# S7G7_footprint_simplified_w_ethernet_v1p.net
KiCad netlist of a schematic drawn in EAGLE
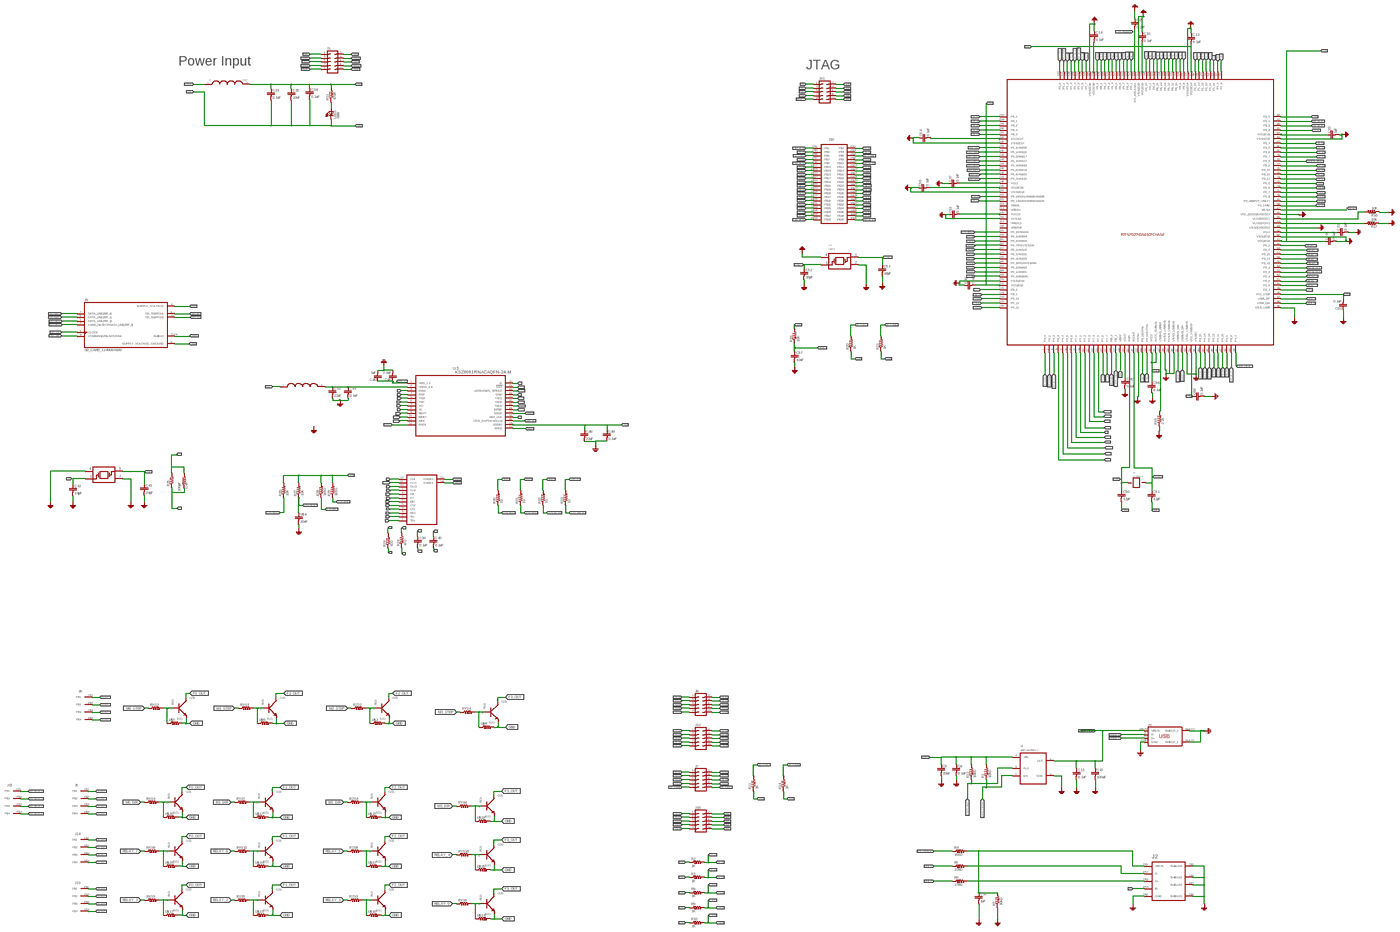
[diagram p0: schematic, sheet 1, overview]
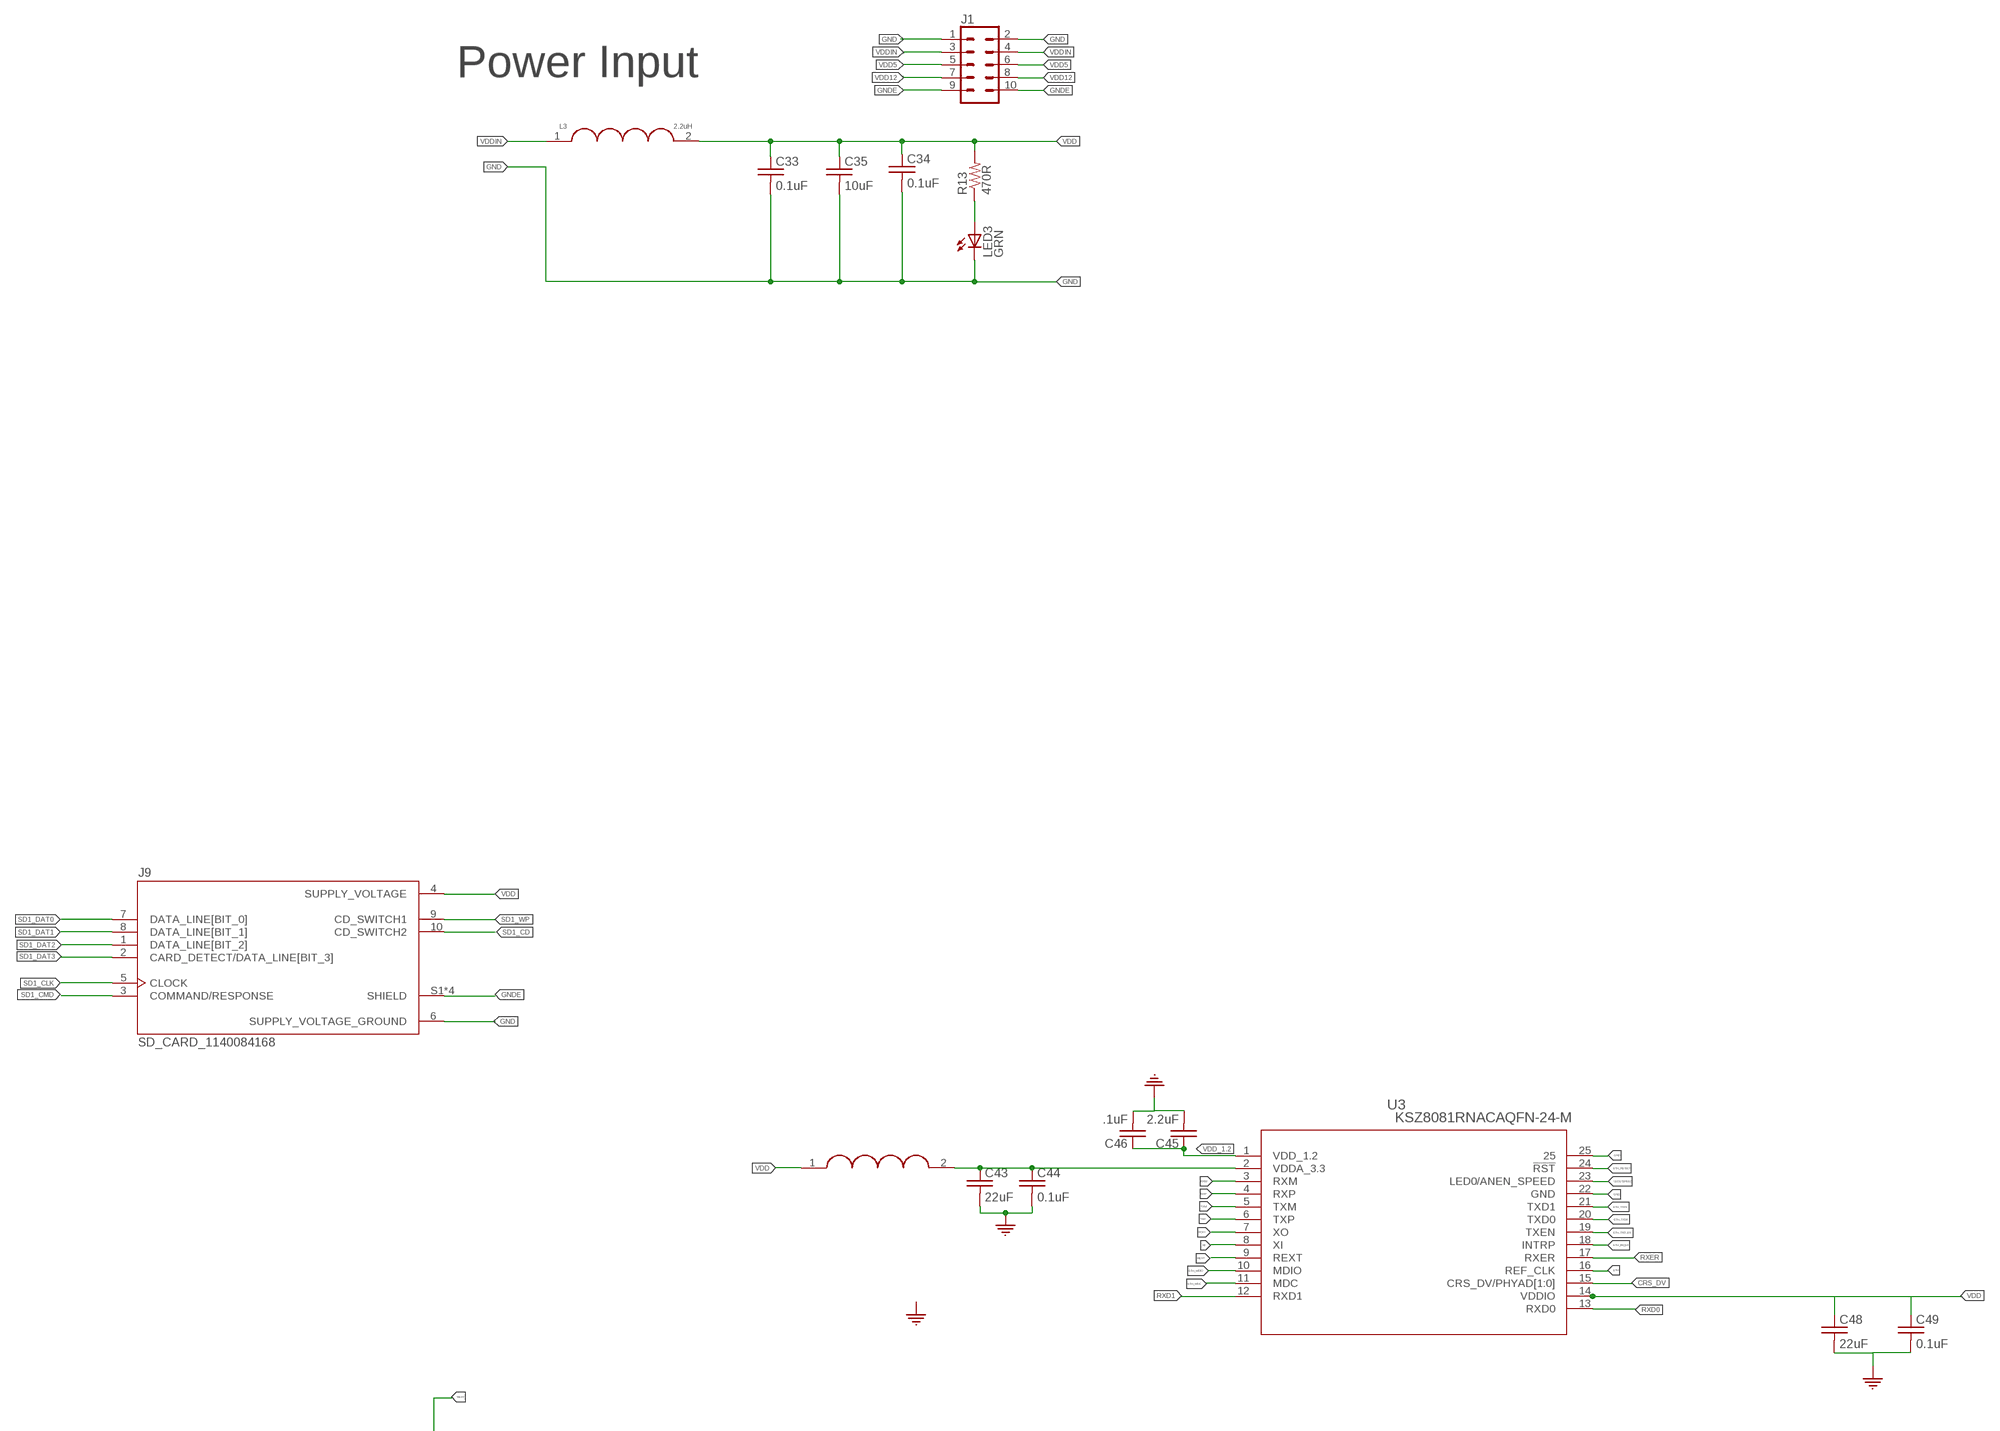
[diagram p1: schematic, sheet 1, part 1 of 4]
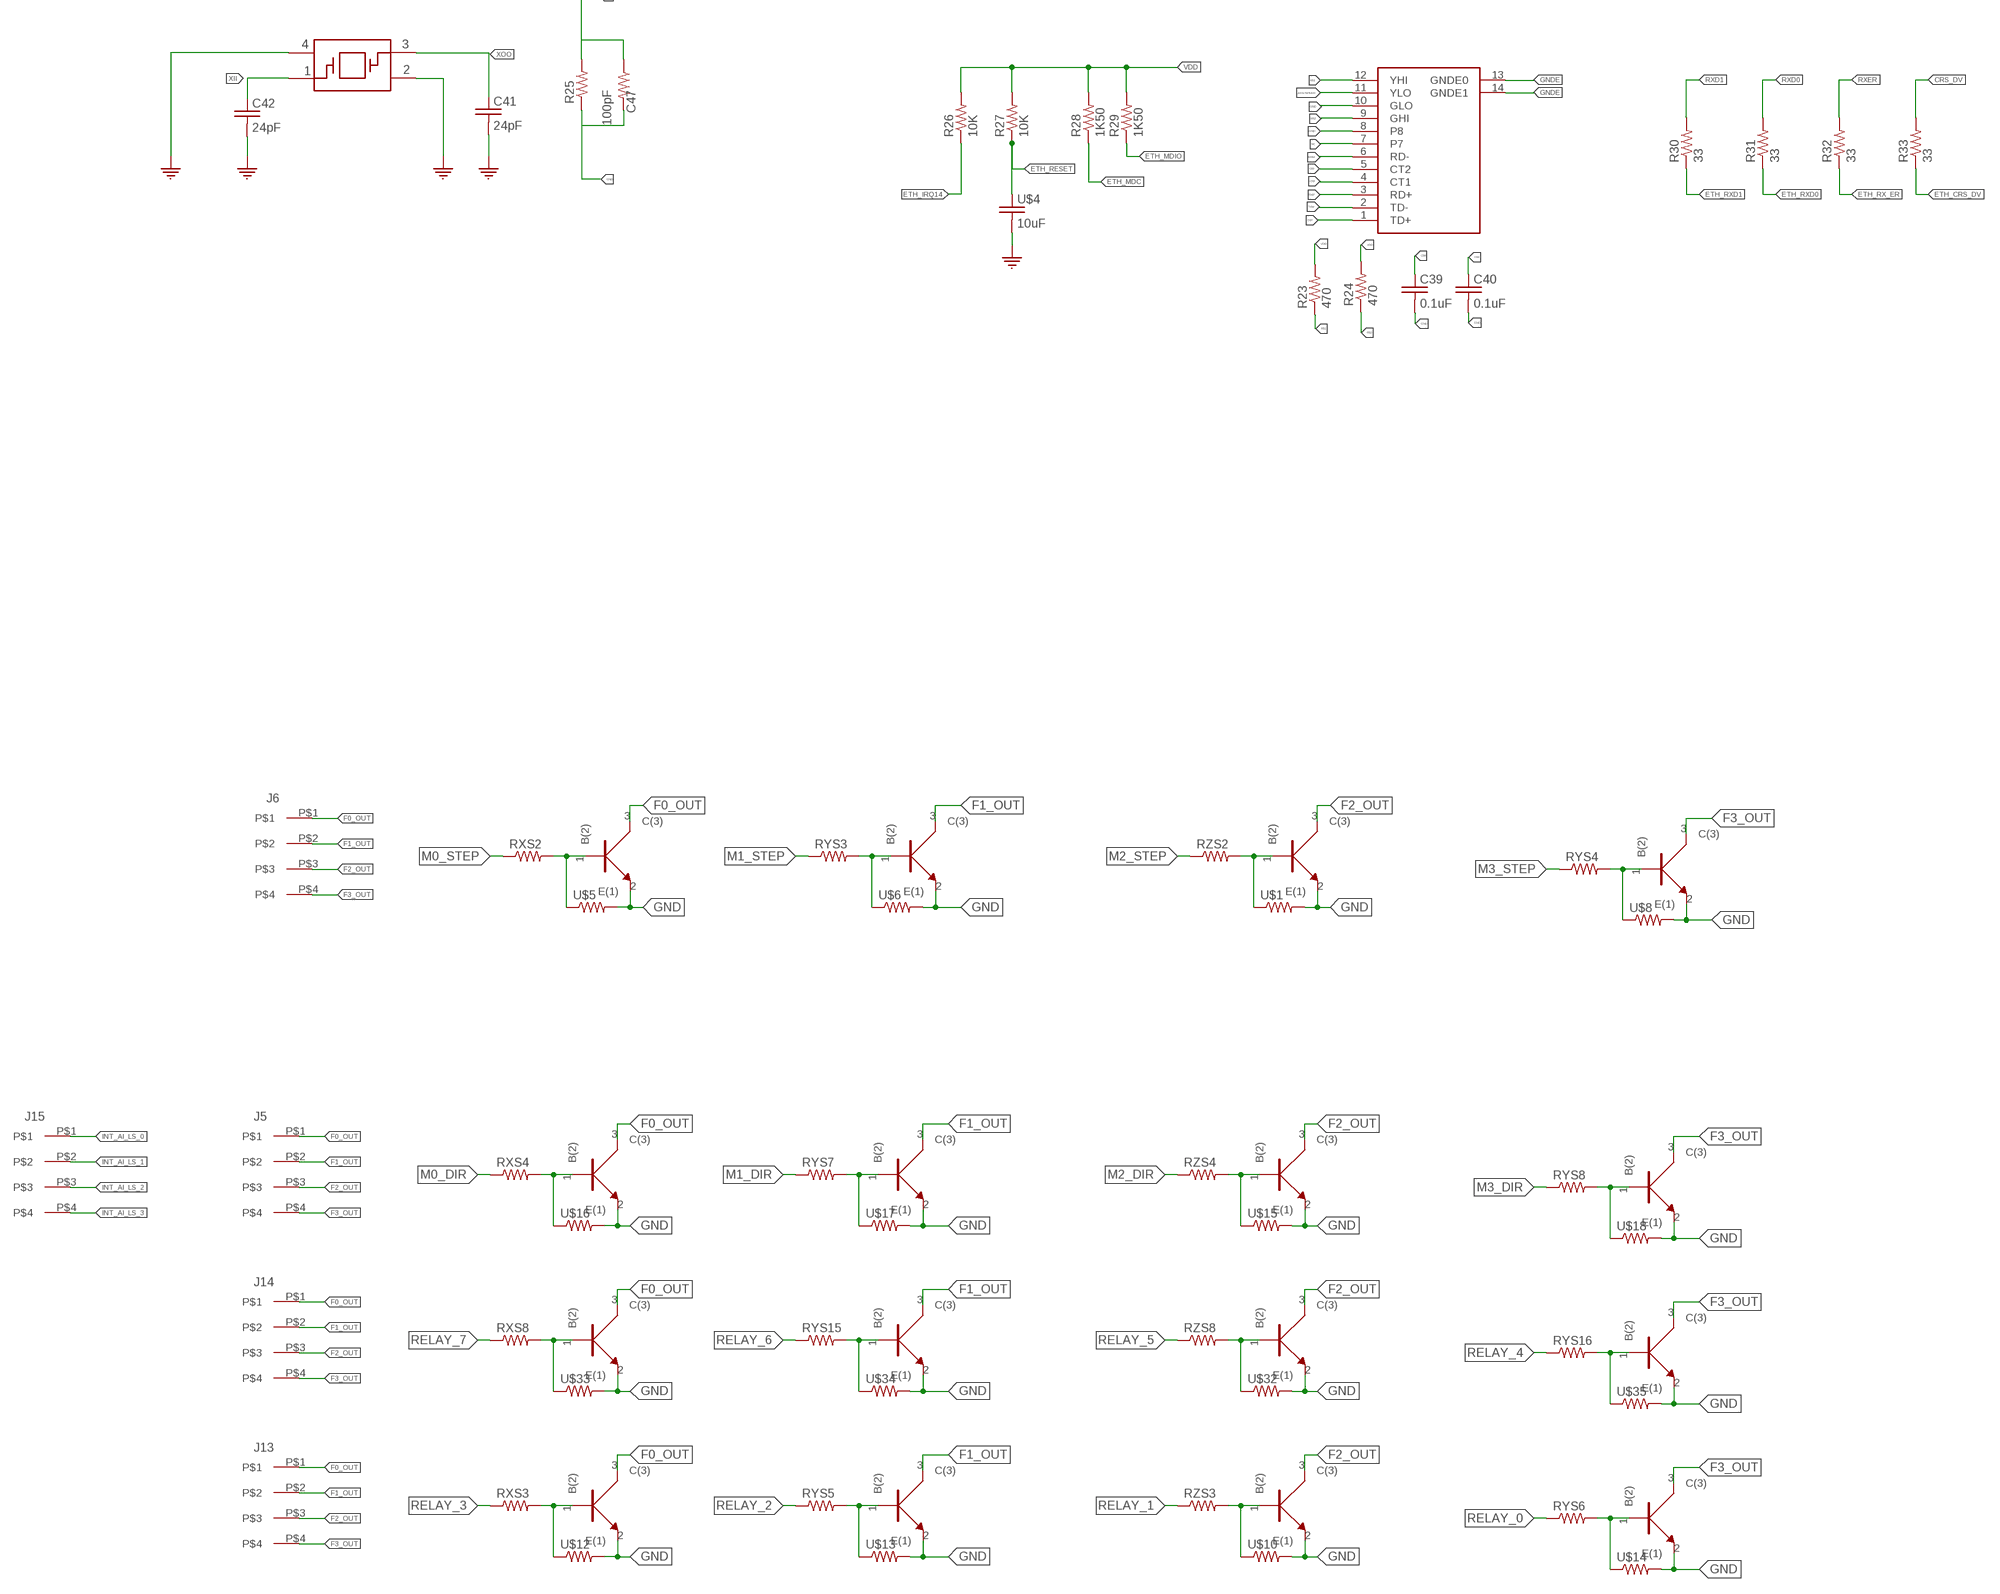
[diagram p2: schematic, sheet 1, part 2 of 4]
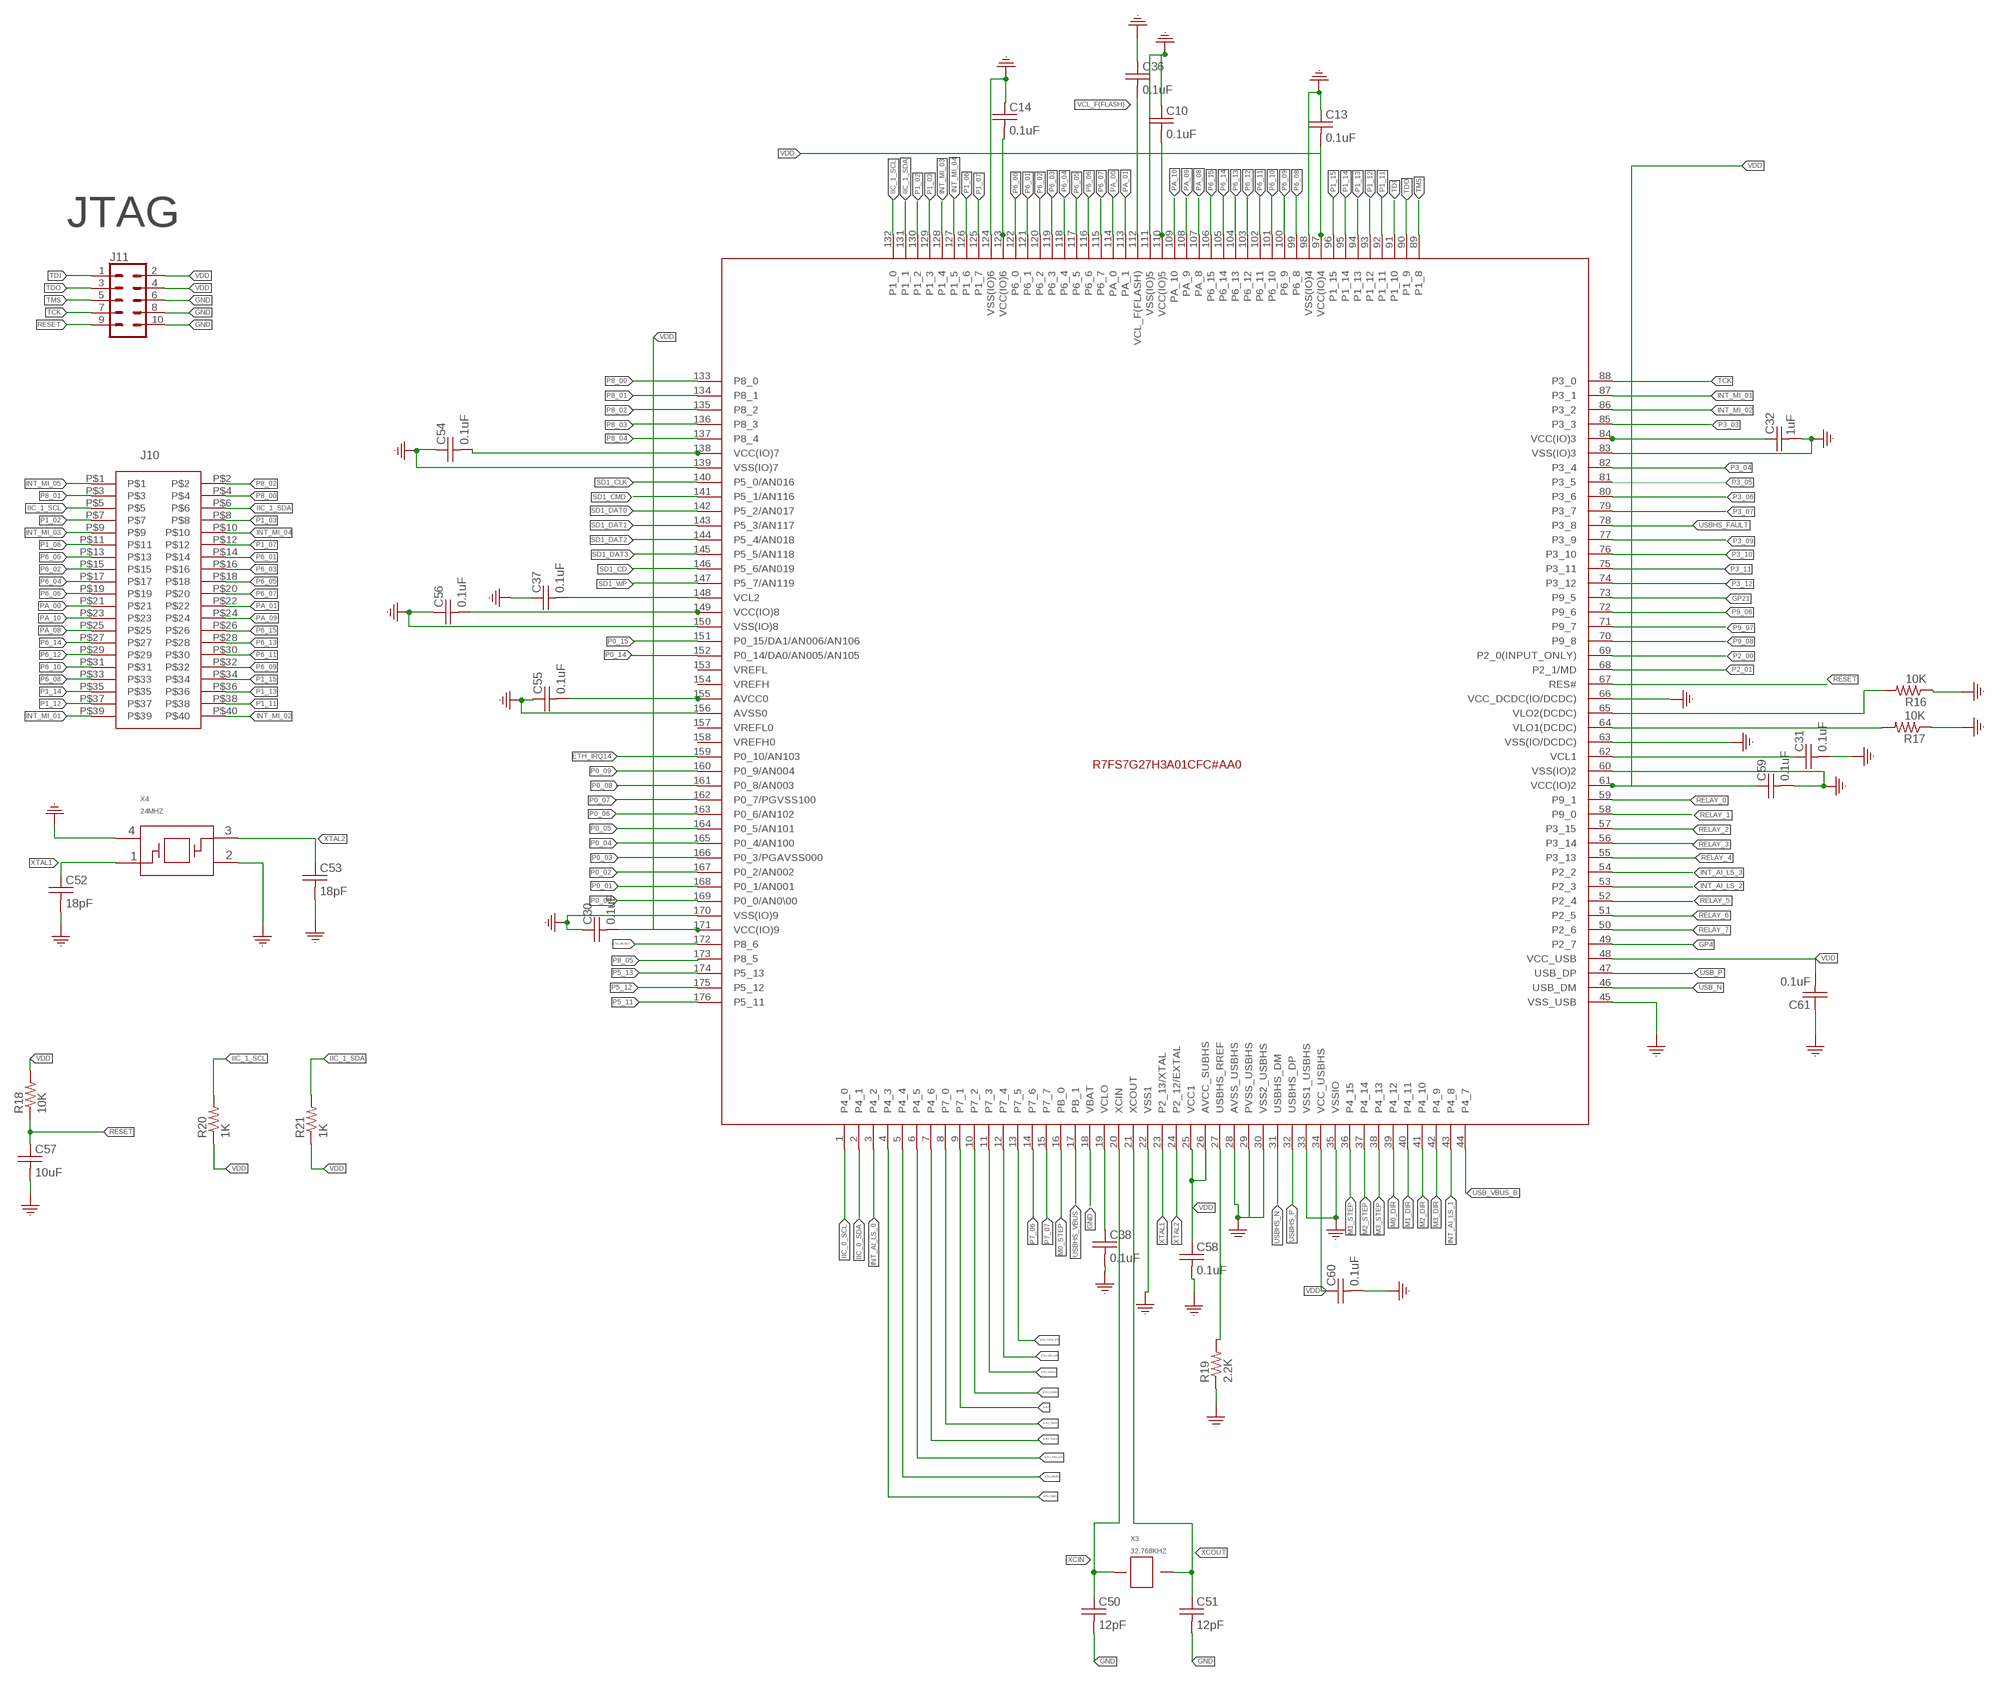
[diagram p3: schematic, sheet 1, part 3 of 4]
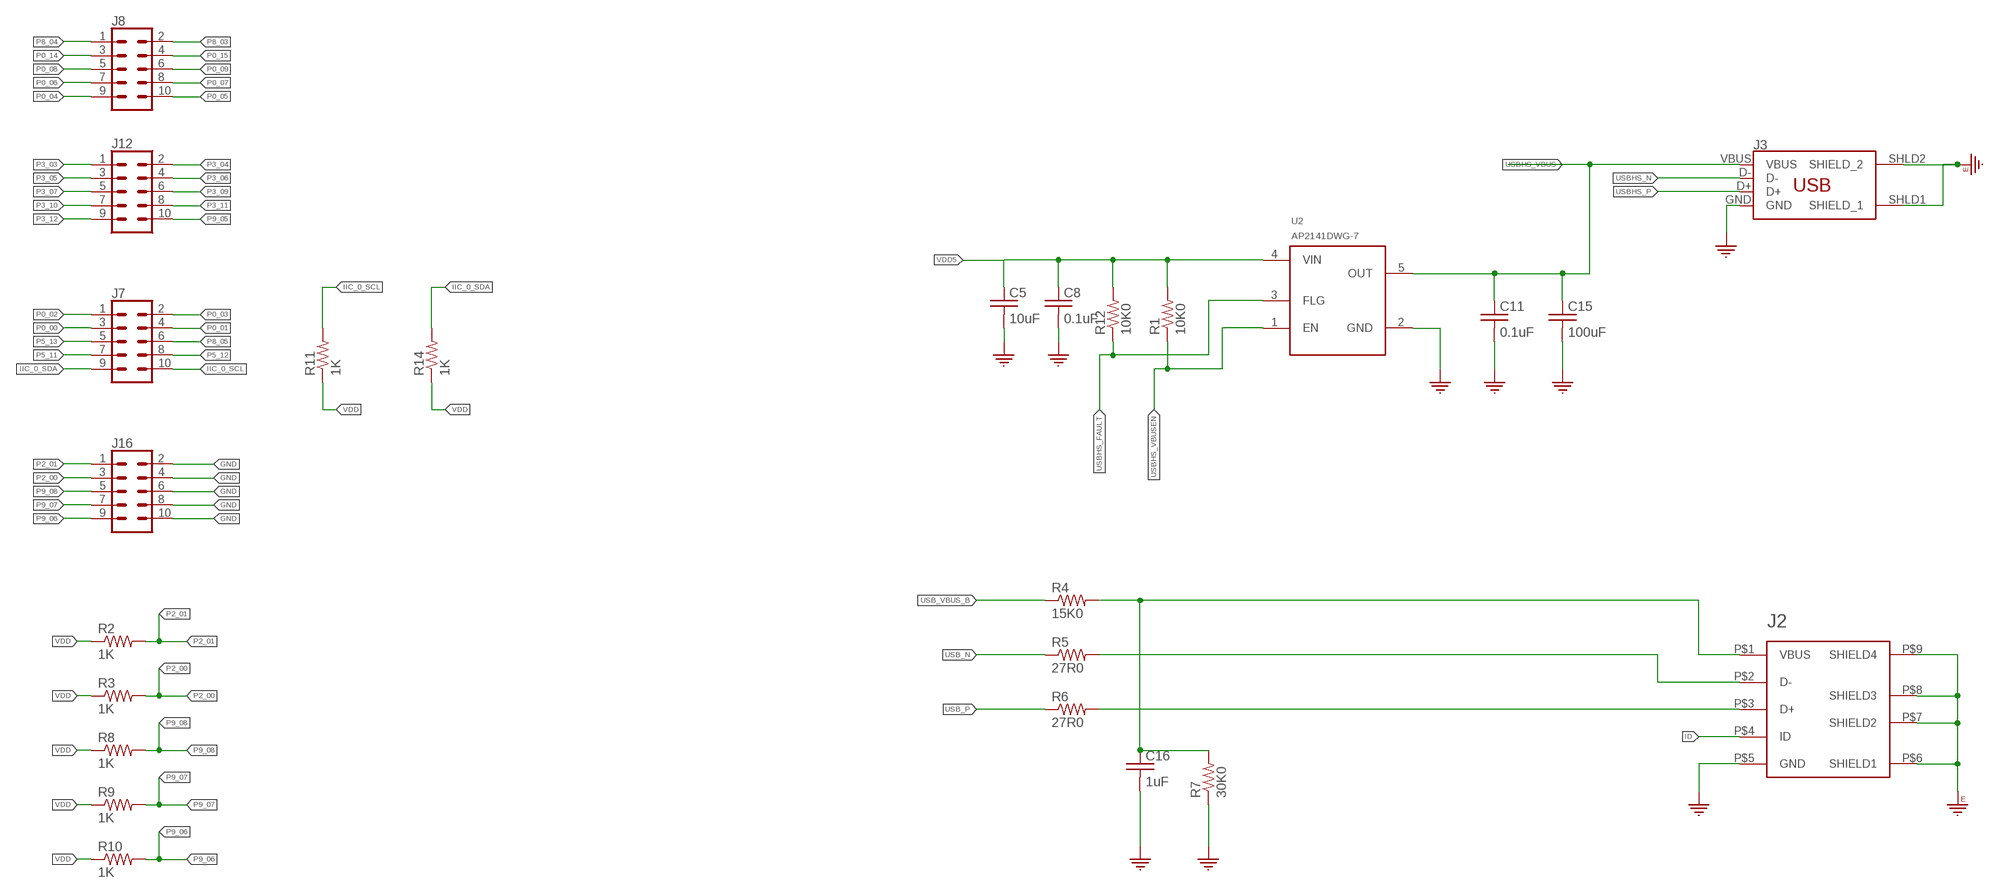
[diagram p4: schematic, sheet 1, part 4 of 4]

(export (version "E")
  (design (tool "Eeschema 10.0.6"))
  (components
    (comp (ref "C5")
      (value "10uF")
      (footprint "eagle-import:0402")
      (libsource (lib "eagle-import") (part "C_0402"))
    )
    (comp (ref "C8")
      (value "0.1uF")
      (footprint "eagle-import:0402")
      (libsource (lib "eagle-import") (part "C_0402"))
    )
    (comp (ref "C10")
      (value "0.1uF")
      (footprint "eagle-import:0402")
      (libsource (lib "eagle-import") (part "C_0402"))
    )
    (comp (ref "C11")
      (value "0.1uF")
      (footprint "eagle-import:0402")
      (libsource (lib "eagle-import") (part "C_0402"))
    )
    (comp (ref "C13")
      (value "0.1uF")
      (footprint "eagle-import:0402")
      (libsource (lib "eagle-import") (part "C_0402"))
    )
    (comp (ref "C14")
      (value "0.1uF")
      (footprint "eagle-import:0402")
      (libsource (lib "eagle-import") (part "C_0402"))
    )
    (comp (ref "C15")
      (value "100uF")
      (footprint "eagle-import:C1210")
      (libsource (lib "eagle-import") (part "C_1210"))
    )
    (comp (ref "C16")
      (value "1uF")
      (footprint "eagle-import:0402")
      (libsource (lib "eagle-import") (part "C_0402"))
    )
    (comp (ref "C30")
      (value "0.1uF")
      (footprint "eagle-import:0402")
      (libsource (lib "eagle-import") (part "C_0402"))
    )
    (comp (ref "C31")
      (value "0.1uF")
      (footprint "eagle-import:0402")
      (libsource (lib "eagle-import") (part "C_0402"))
    )
    (comp (ref "C32")
      (value "1uF")
      (footprint "eagle-import:0402")
      (libsource (lib "eagle-import") (part "C_0402"))
    )
    (comp (ref "C33")
      (value "0.1uF")
      (footprint "eagle-import:0402")
      (libsource (lib "eagle-import") (part "C_0402"))
    )
    (comp (ref "C34")
      (value "0.1uF")
      (footprint "eagle-import:0402")
      (libsource (lib "eagle-import") (part "C_0402"))
    )
    (comp (ref "C35")
      (value "10uF")
      (footprint "eagle-import:0402")
      (libsource (lib "eagle-import") (part "C_0402"))
    )
    (comp (ref "C36")
      (value "0.1uF")
      (footprint "eagle-import:0402")
      (libsource (lib "eagle-import") (part "C_0402"))
    )
    (comp (ref "C37")
      (value "0.1uF")
      (footprint "eagle-import:0402")
      (libsource (lib "eagle-import") (part "C_0402"))
    )
    (comp (ref "C38")
      (value "0.1uF")
      (footprint "eagle-import:0402")
      (libsource (lib "eagle-import") (part "C_0402"))
    )
    (comp (ref "C39")
      (value "0.1uF")
      (footprint "eagle-import:0402")
      (libsource (lib "eagle-import") (part "C_0402"))
    )
    (comp (ref "C40")
      (value "0.1uF")
      (footprint "eagle-import:0402")
      (libsource (lib "eagle-import") (part "C_0402"))
    )
    (comp (ref "C41")
      (value "24pF")
      (footprint "eagle-import:0402")
      (libsource (lib "eagle-import") (part "C_0402"))
    )
    (comp (ref "C42")
      (value "24pF")
      (footprint "eagle-import:0402")
      (libsource (lib "eagle-import") (part "C_0402"))
    )
    (comp (ref "C43")
      (value "22uF")
      (footprint "eagle-import:0603")
      (libsource (lib "eagle-import") (part "C_0603"))
    )
    (comp (ref "C44")
      (value "0.1uF")
      (footprint "eagle-import:0402")
      (libsource (lib "eagle-import") (part "C_0402"))
    )
    (comp (ref "C45")
      (value "2.2uF")
      (footprint "eagle-import:0402")
      (libsource (lib "eagle-import") (part "C_0402"))
    )
    (comp (ref "C46")
      (value ".1uF")
      (footprint "eagle-import:0402")
      (libsource (lib "eagle-import") (part "C_0402"))
    )
    (comp (ref "C47")
      (value "100pF")
      (footprint "eagle-import:0402")
      (libsource (lib "eagle-import") (part "R_0402"))
    )
    (comp (ref "C48")
      (value "22uF")
      (footprint "eagle-import:0603")
      (libsource (lib "eagle-import") (part "C_0603"))
    )
    (comp (ref "C49")
      (value "0.1uF")
      (footprint "eagle-import:0402")
      (libsource (lib "eagle-import") (part "C_0402"))
    )
    (comp (ref "C50")
      (value "12pF")
      (footprint "eagle-import:0402")
      (libsource (lib "eagle-import") (part "C_0402"))
    )
    (comp (ref "C51")
      (value "12pF")
      (footprint "eagle-import:0402")
      (libsource (lib "eagle-import") (part "C_0402"))
    )
    (comp (ref "C52")
      (value "18pF")
      (footprint "eagle-import:0402")
      (libsource (lib "eagle-import") (part "C_0402"))
    )
    (comp (ref "C53")
      (value "18pF")
      (footprint "eagle-import:0402")
      (libsource (lib "eagle-import") (part "C_0402"))
    )
    (comp (ref "C54")
      (value "0.1uF")
      (footprint "eagle-import:0402")
      (libsource (lib "eagle-import") (part "C_0402"))
    )
    (comp (ref "C55")
      (value "0.1uF")
      (footprint "eagle-import:0402")
      (libsource (lib "eagle-import") (part "C_0402"))
    )
    (comp (ref "C56")
      (value "0.1uF")
      (footprint "eagle-import:0402")
      (libsource (lib "eagle-import") (part "C_0402"))
    )
    (comp (ref "C57")
      (value "10uF")
      (footprint "eagle-import:0402")
      (libsource (lib "eagle-import") (part "C_0402"))
    )
    (comp (ref "C58")
      (value "0.1uF")
      (footprint "eagle-import:0402")
      (libsource (lib "eagle-import") (part "C_0402"))
    )
    (comp (ref "C59")
      (value "0.1uF")
      (footprint "eagle-import:0402")
      (libsource (lib "eagle-import") (part "C_0402"))
    )
    (comp (ref "C60")
      (value "0.1uF")
      (footprint "eagle-import:0402")
      (libsource (lib "eagle-import") (part "C_0402"))
    )
    (comp (ref "C61")
      (value "0.1uF")
      (footprint "eagle-import:0402")
      (libsource (lib "eagle-import") (part "C_0402"))
    )
    (comp (ref "FB2/2")
      (value "FB_0805_120_OHM")
      (footprint "eagle-import:0805")
      (libsource (lib "eagle-import") (part "FB_0805_120_OHM"))
    )
    (comp (ref "J1")
      (value "CONN_05X2PTH")
      (footprint "eagle-import:2X5")
      (libsource (lib "eagle-import") (part "CONN_05X2PTH"))
    )
    (comp (ref "J2")
      (value "USB_MICRO-B")
      (footprint "eagle-import:USB_MICRO-B")
      (libsource (lib "eagle-import") (part "USB_MICRO-B"))
    )
    (comp (ref "J3")
      (value "USB_A")
      (footprint "eagle-import:USB_A_SMT")
      (libsource (lib "eagle-import") (part "USB_A"))
    )
    (comp (ref "J4")
      (value "RJ45_WITH_ELEC")
      (footprint "eagle-import:RJ45_TH_ELEC")
      (libsource (lib "eagle-import") (part "RJ45_WITH_ELEC"))
    )
    (comp (ref "J5")
      (value "3.81MM_1_X_4_RT_ANGLE_PLUG_HEADER")
      (footprint "eagle-import:1X4_3.81MM_PITCH")
      (libsource (lib "eagle-import") (part "3.81MM_1_X_4_RT_ANGLE_PLUG_HEADER"))
    )
    (comp (ref "J6")
      (value "3.81MM_1_X_4_RT_ANGLE_PLUG_HEADER")
      (footprint "eagle-import:1X4_3.81MM_PITCH")
      (libsource (lib "eagle-import") (part "3.81MM_1_X_4_RT_ANGLE_PLUG_HEADER"))
    )
    (comp (ref "J7")
      (value "CONN_05X2NO_SILK")
      (footprint "eagle-import:2X5_NOSILK")
      (libsource (lib "eagle-import") (part "CONN_05X2NO_SILK"))
    )
    (comp (ref "J8")
      (value "CONN_05X2NO_SILK")
      (footprint "eagle-import:2X5_NOSILK")
      (libsource (lib "eagle-import") (part "CONN_05X2NO_SILK"))
    )
    (comp (ref "J9")
      (value "SD_CARD_1140084168")
      (footprint "eagle-import:AMPHENOL_1140084168")
      (fields
        (field (name "DIGI-KEY_PART_NUMBER") "114-00841-68-1-ND")
        (field (name "MF") "Amphenol ICC")
        (field (name "MP") "114-00841-68")
      )
      (libsource (lib "eagle-import") (part "SD_CARD_1140084168"))
    )
    (comp (ref "J10")
      (value "HEADER_2_X_20_GENERIC")
      (footprint "eagle-import:HEADER_2_X_20_.1_INCH")
      (libsource (lib "eagle-import") (part "HEADER_2_X_20_GENERIC"))
    )
    (comp (ref "J11")
      (value "CONN_05X2PTH")
      (footprint "eagle-import:2X5")
      (libsource (lib "eagle-import") (part "CONN_05X2PTH"))
    )
    (comp (ref "J12")
      (value "CONN_05X2NO_SILK")
      (footprint "eagle-import:2X5_NOSILK")
      (libsource (lib "eagle-import") (part "CONN_05X2NO_SILK"))
    )
    (comp (ref "J13")
      (value "3.81MM_1_X_4_RT_ANGLE_PLUG_HEADER")
      (footprint "eagle-import:1X4_3.81MM_PITCH")
      (libsource (lib "eagle-import") (part "3.81MM_1_X_4_RT_ANGLE_PLUG_HEADER"))
    )
    (comp (ref "J14")
      (value "3.81MM_1_X_4_RT_ANGLE_PLUG_HEADER")
      (footprint "eagle-import:1X4_3.81MM_PITCH")
      (libsource (lib "eagle-import") (part "3.81MM_1_X_4_RT_ANGLE_PLUG_HEADER"))
    )
    (comp (ref "J15")
      (value "3.81MM_1_X_4_RT_ANGLE_PLUG_HEADER")
      (footprint "eagle-import:1X4_3.81MM_PITCH")
      (libsource (lib "eagle-import") (part "3.81MM_1_X_4_RT_ANGLE_PLUG_HEADER"))
    )
    (comp (ref "J16")
      (value "CONN_05X2SHD_SMD")
      (footprint "eagle-import:2X5-SHROUDED_SMD")
      (libsource (lib "eagle-import") (part "CONN_05X2SHD_SMD"))
    )
    (comp (ref "L3")
      (value "2.2uH")
      (footprint "eagle-import:1008_(2520_METRIC)")
      (libsource (lib "eagle-import") (part "INDUCTOR_1008_2.2_MH_1.3A"))
    )
    (comp (ref "LED3")
      (value "LED_0805_GREEN")
      (footprint "eagle-import:LED_0805_GREEN")
      (libsource (lib "eagle-import") (part "LED_0805_GREEN"))
    )
    (comp (ref "R1")
      (value "10K0")
      (footprint "eagle-import:0402")
      (libsource (lib "eagle-import") (part "R_0402"))
    )
    (comp (ref "R2")
      (value "1K")
      (footprint "eagle-import:0402")
      (libsource (lib "eagle-import") (part "R_0402"))
    )
    (comp (ref "R3")
      (value "1K")
      (footprint "eagle-import:0402")
      (libsource (lib "eagle-import") (part "R_0402"))
    )
    (comp (ref "R4")
      (value "15K0")
      (footprint "eagle-import:0402")
      (libsource (lib "eagle-import") (part "R_0402"))
    )
    (comp (ref "R5")
      (value "27R0")
      (footprint "eagle-import:0402")
      (libsource (lib "eagle-import") (part "R_0402"))
    )
    (comp (ref "R6")
      (value "27R0")
      (footprint "eagle-import:0402")
      (libsource (lib "eagle-import") (part "R_0402"))
    )
    (comp (ref "R7")
      (value "30K0")
      (footprint "eagle-import:0402")
      (libsource (lib "eagle-import") (part "R_0402"))
    )
    (comp (ref "R8")
      (value "1K")
      (footprint "eagle-import:0402")
      (libsource (lib "eagle-import") (part "R_0402"))
    )
    (comp (ref "R9")
      (value "1K")
      (footprint "eagle-import:0402")
      (libsource (lib "eagle-import") (part "R_0402"))
    )
    (comp (ref "R10")
      (value "1K")
      (footprint "eagle-import:0402")
      (libsource (lib "eagle-import") (part "R_0402"))
    )
    (comp (ref "R11")
      (value "1K")
      (footprint "eagle-import:0402")
      (libsource (lib "eagle-import") (part "R_0402"))
    )
    (comp (ref "R12")
      (value "10K0")
      (footprint "eagle-import:0402")
      (libsource (lib "eagle-import") (part "R_0402"))
    )
    (comp (ref "R13")
      (value "470R")
      (footprint "eagle-import:0402")
      (libsource (lib "eagle-import") (part "R_0402"))
    )
    (comp (ref "R14")
      (value "1K")
      (footprint "eagle-import:0402")
      (libsource (lib "eagle-import") (part "R_0402"))
    )
    (comp (ref "R16")
      (value "10K")
      (footprint "eagle-import:0402")
      (libsource (lib "eagle-import") (part "R_0402"))
    )
    (comp (ref "R17")
      (value "10K")
      (footprint "eagle-import:0402")
      (libsource (lib "eagle-import") (part "R_0402"))
    )
    (comp (ref "R18")
      (value "10K")
      (footprint "eagle-import:0402")
      (libsource (lib "eagle-import") (part "R_0402"))
    )
    (comp (ref "R19")
      (value "2.2K")
      (footprint "eagle-import:0402")
      (libsource (lib "eagle-import") (part "R_0402"))
    )
    (comp (ref "R20")
      (value "1K")
      (footprint "eagle-import:0402")
      (libsource (lib "eagle-import") (part "R_0402"))
    )
    (comp (ref "R21")
      (value "1K")
      (footprint "eagle-import:0402")
      (libsource (lib "eagle-import") (part "R_0402"))
    )
    (comp (ref "R23")
      (value "470")
      (footprint "eagle-import:0402")
      (libsource (lib "eagle-import") (part "R_0402"))
    )
    (comp (ref "R24")
      (value "470")
      (footprint "eagle-import:0402")
      (libsource (lib "eagle-import") (part "R_0402"))
    )
    (comp (ref "R25")
      (value "6k49")
      (footprint "eagle-import:0402")
      (libsource (lib "eagle-import") (part "R_0402"))
    )
    (comp (ref "R26")
      (value "10K")
      (footprint "eagle-import:0402")
      (libsource (lib "eagle-import") (part "R_0402"))
    )
    (comp (ref "R27")
      (value "10K")
      (footprint "eagle-import:0402")
      (libsource (lib "eagle-import") (part "R_0402"))
    )
    (comp (ref "R28")
      (value "1K50")
      (footprint "eagle-import:0402")
      (libsource (lib "eagle-import") (part "R_0402"))
    )
    (comp (ref "R29")
      (value "1K50")
      (footprint "eagle-import:0402")
      (libsource (lib "eagle-import") (part "R_0402"))
    )
    (comp (ref "R30")
      (value "33")
      (footprint "eagle-import:0402")
      (libsource (lib "eagle-import") (part "R_0402"))
    )
    (comp (ref "R31")
      (value "33")
      (footprint "eagle-import:0402")
      (libsource (lib "eagle-import") (part "R_0402"))
    )
    (comp (ref "R32")
      (value "33")
      (footprint "eagle-import:0402")
      (libsource (lib "eagle-import") (part "R_0402"))
    )
    (comp (ref "R33")
      (value "33")
      (footprint "eagle-import:0402")
      (libsource (lib "eagle-import") (part "R_0402"))
    )
    (comp (ref "RXS2")
      (value "1K")
      (footprint "eagle-import:0402")
      (libsource (lib "eagle-import") (part "R_0402"))
    )
    (comp (ref "RXS3")
      (value "1K")
      (footprint "eagle-import:0402")
      (libsource (lib "eagle-import") (part "R_0402"))
    )
    (comp (ref "RXS4")
      (value "1K")
      (footprint "eagle-import:0402")
      (libsource (lib "eagle-import") (part "R_0402"))
    )
    (comp (ref "RXS8")
      (value "1K")
      (footprint "eagle-import:0402")
      (libsource (lib "eagle-import") (part "R_0402"))
    )
    (comp (ref "RYS3")
      (value "1K")
      (footprint "eagle-import:0402")
      (libsource (lib "eagle-import") (part "R_0402"))
    )
    (comp (ref "RYS4")
      (value "1K")
      (footprint "eagle-import:0402")
      (libsource (lib "eagle-import") (part "R_0402"))
    )
    (comp (ref "RYS5")
      (value "1K")
      (footprint "eagle-import:0402")
      (libsource (lib "eagle-import") (part "R_0402"))
    )
    (comp (ref "RYS6")
      (value "1K")
      (footprint "eagle-import:0402")
      (libsource (lib "eagle-import") (part "R_0402"))
    )
    (comp (ref "RYS7")
      (value "1K")
      (footprint "eagle-import:0402")
      (libsource (lib "eagle-import") (part "R_0402"))
    )
    (comp (ref "RYS8")
      (value "1K")
      (footprint "eagle-import:0402")
      (libsource (lib "eagle-import") (part "R_0402"))
    )
    (comp (ref "RYS15")
      (value "1K")
      (footprint "eagle-import:0402")
      (libsource (lib "eagle-import") (part "R_0402"))
    )
    (comp (ref "RYS16")
      (value "1K")
      (footprint "eagle-import:0402")
      (libsource (lib "eagle-import") (part "R_0402"))
    )
    (comp (ref "RZS2")
      (value "1K")
      (footprint "eagle-import:0402")
      (libsource (lib "eagle-import") (part "R_0402"))
    )
    (comp (ref "RZS3")
      (value "1K")
      (footprint "eagle-import:0402")
      (libsource (lib "eagle-import") (part "R_0402"))
    )
    (comp (ref "RZS4")
      (value "1K")
      (footprint "eagle-import:0402")
      (libsource (lib "eagle-import") (part "R_0402"))
    )
    (comp (ref "RZS8")
      (value "1K")
      (footprint "eagle-import:0402")
      (libsource (lib "eagle-import") (part "R_0402"))
    )
    (comp (ref "U$1")
      (value "1K")
      (footprint "eagle-import:0402")
      (libsource (lib "eagle-import") (part "R_0402"))
    )
    (comp (ref "U$3")
      (value "XTAL_25_MHZ")
      (footprint "eagle-import:SMD_3225")
      (libsource (lib "eagle-import") (part "XTAL_25_MHZ"))
    )
    (comp (ref "U$4")
      (value "10uF")
      (footprint "eagle-import:0402")
      (libsource (lib "eagle-import") (part "C_0402"))
    )
    (comp (ref "U$5")
      (value "1K")
      (footprint "eagle-import:0402")
      (libsource (lib "eagle-import") (part "R_0402"))
    )
    (comp (ref "U$6")
      (value "1K")
      (footprint "eagle-import:0402")
      (libsource (lib "eagle-import") (part "R_0402"))
    )
    (comp (ref "U$8")
      (value "1K")
      (footprint "eagle-import:0402")
      (libsource (lib "eagle-import") (part "R_0402"))
    )
    (comp (ref "U$10")
      (value "1K")
      (footprint "eagle-import:0402")
      (libsource (lib "eagle-import") (part "R_0402"))
    )
    (comp (ref "U$12")
      (value "1K")
      (footprint "eagle-import:0402")
      (libsource (lib "eagle-import") (part "R_0402"))
    )
    (comp (ref "U$13")
      (value "1K")
      (footprint "eagle-import:0402")
      (libsource (lib "eagle-import") (part "R_0402"))
    )
    (comp (ref "U$14")
      (value "1K")
      (footprint "eagle-import:0402")
      (libsource (lib "eagle-import") (part "R_0402"))
    )
    (comp (ref "U$15")
      (value "1K")
      (footprint "eagle-import:0402")
      (libsource (lib "eagle-import") (part "R_0402"))
    )
    (comp (ref "U$16")
      (value "1K")
      (footprint "eagle-import:0402")
      (libsource (lib "eagle-import") (part "R_0402"))
    )
    (comp (ref "U$17")
      (value "1K")
      (footprint "eagle-import:0402")
      (libsource (lib "eagle-import") (part "R_0402"))
    )
    (comp (ref "U$18")
      (value "1K")
      (footprint "eagle-import:0402")
      (libsource (lib "eagle-import") (part "R_0402"))
    )
    (comp (ref "U$32")
      (value "1K")
      (footprint "eagle-import:0402")
      (libsource (lib "eagle-import") (part "R_0402"))
    )
    (comp (ref "U$33")
      (value "1K")
      (footprint "eagle-import:0402")
      (libsource (lib "eagle-import") (part "R_0402"))
    )
    (comp (ref "U$34")
      (value "1K")
      (footprint "eagle-import:0402")
      (libsource (lib "eagle-import") (part "R_0402"))
    )
    (comp (ref "U$35")
      (value "1K")
      (footprint "eagle-import:0402")
      (libsource (lib "eagle-import") (part "R_0402"))
    )
    (comp (ref "U2")
      (value "AP2141DWG-5")
      (footprint "eagle-import:SOT-23-5")
      (libsource (lib "eagle-import") (part "AP2141DWG-5"))
    )
    (comp (ref "U3")
      (value "KSZ8081RNACAQFN-24-M")
      (footprint "eagle-import:QFN-24-M")
      (fields (field (name "MANUFACTURER_PART_NUMBER") "KSZ8081RNACA"))
      (libsource (lib "eagle-import") (part "KSZ8081RNACAQFN-24-M"))
    )
    (comp (ref "U4")
      (value "S7G2_X_176")
      (footprint "eagle-import:LQFP176_24X24")
      (libsource (lib "eagle-import") (part "S7G2_X_176"))
    )
    (comp (ref "U7")
      (value "BC846BW")
      (footprint "eagle-import:SOT323")
      (libsource (lib "eagle-import") (part "BC846BW"))
    )
    (comp (ref "U8")
      (value "BC846BW")
      (footprint "eagle-import:SOT323")
      (libsource (lib "eagle-import") (part "BC846BW"))
    )
    (comp (ref "U9")
      (value "BC846BW")
      (footprint "eagle-import:SOT323")
      (libsource (lib "eagle-import") (part "BC846BW"))
    )
    (comp (ref "U10")
      (value "BC846BW")
      (footprint "eagle-import:SOT323")
      (libsource (lib "eagle-import") (part "BC846BW"))
    )
    (comp (ref "U12")
      (value "BC846BW")
      (footprint "eagle-import:SOT323")
      (libsource (lib "eagle-import") (part "BC846BW"))
    )
    (comp (ref "U13")
      (value "BC846BW")
      (footprint "eagle-import:SOT323")
      (libsource (lib "eagle-import") (part "BC846BW"))
    )
    (comp (ref "U14")
      (value "BC846BW")
      (footprint "eagle-import:SOT323")
      (libsource (lib "eagle-import") (part "BC846BW"))
    )
    (comp (ref "U15")
      (value "BC846BW")
      (footprint "eagle-import:SOT323")
      (libsource (lib "eagle-import") (part "BC846BW"))
    )
    (comp (ref "U16")
      (value "BC846BW")
      (footprint "eagle-import:SOT323")
      (libsource (lib "eagle-import") (part "BC846BW"))
    )
    (comp (ref "U17")
      (value "BC846BW")
      (footprint "eagle-import:SOT323")
      (libsource (lib "eagle-import") (part "BC846BW"))
    )
    (comp (ref "U18")
      (value "BC846BW")
      (footprint "eagle-import:SOT323")
      (libsource (lib "eagle-import") (part "BC846BW"))
    )
    (comp (ref "U19")
      (value "BC846BW")
      (footprint "eagle-import:SOT323")
      (libsource (lib "eagle-import") (part "BC846BW"))
    )
    (comp (ref "U32")
      (value "BC846BW")
      (footprint "eagle-import:SOT323")
      (libsource (lib "eagle-import") (part "BC846BW"))
    )
    (comp (ref "U33")
      (value "BC846BW")
      (footprint "eagle-import:SOT323")
      (libsource (lib "eagle-import") (part "BC846BW"))
    )
    (comp (ref "U34")
      (value "BC846BW")
      (footprint "eagle-import:SOT323")
      (libsource (lib "eagle-import") (part "BC846BW"))
    )
    (comp (ref "U35")
      (value "BC846BW")
      (footprint "eagle-import:SOT323")
      (libsource (lib "eagle-import") (part "BC846BW"))
    )
    (comp (ref "X3")
      (value "32.768KHZ")
      (footprint "eagle-import:SMD_X_2_PADS")
      (libsource (lib "eagle-import") (part "XTAL_32.768KHZ"))
    )
    (comp (ref "X4")
      (value "24MHZ")
      (footprint "eagle-import:SMD_3225")
      (libsource (lib "eagle-import") (part "XTAL_24_MHZ"))
    )
  )
  (nets
    (net (code "1") (name "C58") (class "Default")
      (node (ref "C39") (pin "P$1") (pinfunction "1_P$1") (pintype "passive"))
      (node (ref "J4") (pin "4") (pinfunction "CT1_4") (pintype "bidirectional"))
    )
    (net (code "2") (name "C60") (class "Default")
      (node (ref "C40") (pin "P$1") (pinfunction "1_P$1") (pintype "passive"))
      (node (ref "J4") (pin "5") (pinfunction "CT2_5") (pintype "bidirectional"))
    )
    (net (code "3") (name "CRS_DV") (class "Default")
      (node (ref "R33") (pin "P$2") (pinfunction "2_P$2") (pintype "passive"))
      (node (ref "U3") (pin "15") (pinfunction "CRS_DV/PHYAD[1:0]_15") (pintype "bidirectional"))
    )
    (net (code "4") (name "ETH") (class "Default")
      (node (ref "U3") (pin "16") (pinfunction "REF_CLK_16") (pintype "bidirectional"))
      (node (ref "U4") (pin "9") (pinfunction "P7_1_9") (pintype "bidirectional"))
    )
    (net (code "5") (name "ETH_CRS_DV") (class "Default")
      (node (ref "R33") (pin "P$1") (pinfunction "1_P$1") (pintype "passive"))
      (node (ref "U4") (pin "13") (pinfunction "P7_5_13") (pintype "bidirectional"))
    )
    (net (code "6") (name "ETH_IRQ14") (class "Default")
      (node (ref "R26") (pin "P$1") (pinfunction "1_P$1") (pintype "passive"))
      (node (ref "U3") (pin "18") (pinfunction "INTRP_18") (pintype "bidirectional"))
      (node (ref "U4") (pin "159") (pinfunction "P0_10/AN103_159") (pintype "bidirectional"))
    )
    (net (code "7") (name "ETH_MDC") (class "Default")
      (node (ref "R28") (pin "P$1") (pinfunction "1_P$1") (pintype "passive"))
      (node (ref "U3") (pin "11") (pinfunction "MDC_11") (pintype "input"))
      (node (ref "U4") (pin "4") (pinfunction "P4_3_4") (pintype "bidirectional"))
    )
    (net (code "8") (name "ETH_MDIO") (class "Default")
      (node (ref "R29") (pin "P$1") (pinfunction "1_P$1") (pintype "passive"))
      (node (ref "U3") (pin "10") (pinfunction "MDIO_10") (pintype "bidirectional"))
      (node (ref "U4") (pin "5") (pinfunction "P4_4_5") (pintype "bidirectional"))
    )
    (net (code "9") (name "ETH_RESET") (class "Default")
      (node (ref "R27") (pin "P$1") (pinfunction "1_P$1") (pintype "passive"))
      (node (ref "U$4") (pin "P$1") (pinfunction "1_P$1") (pintype "passive"))
      (node (ref "U3") (pin "24") (pinfunction "~{RST}_24") (pintype "input"))
      (node (ref "U4") (pin "172") (pinfunction "P8_6_172") (pintype "bidirectional"))
    )
    (net (code "10") (name "ETH_RXD0") (class "Default")
      (node (ref "R31") (pin "P$1") (pinfunction "1_P$1") (pintype "passive"))
      (node (ref "U4") (pin "10") (pinfunction "P7_2_10") (pintype "bidirectional"))
    )
    (net (code "11") (name "ETH_RXD1") (class "Default")
      (node (ref "R30") (pin "P$1") (pinfunction "1_P$1") (pintype "passive"))
      (node (ref "U4") (pin "11") (pinfunction "P7_3_11") (pintype "bidirectional"))
    )
    (net (code "12") (name "ETH_RX_ER") (class "Default")
      (node (ref "R32") (pin "P$1") (pinfunction "1_P$1") (pintype "passive"))
      (node (ref "U4") (pin "12") (pinfunction "P7_4_12") (pintype "bidirectional"))
    )
    (net (code "13") (name "ETH_TXD0") (class "Default")
      (node (ref "U3") (pin "20") (pinfunction "TXD0_20") (pintype "input"))
      (node (ref "U4") (pin "8") (pinfunction "P7_0_8") (pintype "bidirectional"))
    )
    (net (code "14") (name "ETH_TXD1") (class "Default")
      (node (ref "U3") (pin "21") (pinfunction "TXD1_21") (pintype "bidirectional"))
      (node (ref "U4") (pin "7") (pinfunction "P4_6_7") (pintype "bidirectional"))
    )
    (net (code "15") (name "ETH_TXD_EN") (class "Default")
      (node (ref "U3") (pin "19") (pinfunction "TXEN_19") (pintype "input"))
      (node (ref "U4") (pin "6") (pinfunction "P4_5_6") (pintype "bidirectional"))
    )
    (net (code "16") (name "F0_OUT") (class "Default")
      (node (ref "J13") (pin "P$1") (pinfunction "P$1_P$1") (pintype "bidirectional"))
      (node (ref "J14") (pin "P$1") (pinfunction "P$1_P$1") (pintype "bidirectional"))
      (node (ref "J5") (pin "P$1") (pinfunction "P$1_P$1") (pintype "bidirectional"))
      (node (ref "J6") (pin "P$1") (pinfunction "P$1_P$1") (pintype "bidirectional"))
      (node (ref "U13") (pin "3") (pinfunction "C(3)_3") (pintype "input"))
      (node (ref "U17") (pin "3") (pinfunction "C(3)_3") (pintype "input"))
      (node (ref "U33") (pin "3") (pinfunction "C(3)_3") (pintype "input"))
      (node (ref "U8") (pin "3") (pinfunction "C(3)_3") (pintype "input"))
    )
    (net (code "17") (name "F1_OUT") (class "Default")
      (node (ref "J13") (pin "P$2") (pinfunction "P$2_P$2") (pintype "bidirectional"))
      (node (ref "J14") (pin "P$2") (pinfunction "P$2_P$2") (pintype "bidirectional"))
      (node (ref "J5") (pin "P$2") (pinfunction "P$2_P$2") (pintype "bidirectional"))
      (node (ref "J6") (pin "P$2") (pinfunction "P$2_P$2") (pintype "bidirectional"))
      (node (ref "U14") (pin "3") (pinfunction "C(3)_3") (pintype "input"))
      (node (ref "U18") (pin "3") (pinfunction "C(3)_3") (pintype "input"))
      (node (ref "U34") (pin "3") (pinfunction "C(3)_3") (pintype "input"))
      (node (ref "U9") (pin "3") (pinfunction "C(3)_3") (pintype "input"))
    )
    (net (code "18") (name "F2_OUT") (class "Default")
      (node (ref "J13") (pin "P$3") (pinfunction "P$3_P$3") (pintype "bidirectional"))
      (node (ref "J14") (pin "P$3") (pinfunction "P$3_P$3") (pintype "bidirectional"))
      (node (ref "J5") (pin "P$3") (pinfunction "P$3_P$3") (pintype "bidirectional"))
      (node (ref "J6") (pin "P$3") (pinfunction "P$3_P$3") (pintype "bidirectional"))
      (node (ref "U12") (pin "3") (pinfunction "C(3)_3") (pintype "input"))
      (node (ref "U16") (pin "3") (pinfunction "C(3)_3") (pintype "input"))
      (node (ref "U32") (pin "3") (pinfunction "C(3)_3") (pintype "input"))
      (node (ref "U7") (pin "3") (pinfunction "C(3)_3") (pintype "input"))
    )
    (net (code "19") (name "F3_OUT") (class "Default")
      (node (ref "J13") (pin "P$4") (pinfunction "P$4_P$4") (pintype "bidirectional"))
      (node (ref "J14") (pin "P$4") (pinfunction "P$4_P$4") (pintype "bidirectional"))
      (node (ref "J5") (pin "P$4") (pinfunction "P$4_P$4") (pintype "bidirectional"))
      (node (ref "J6") (pin "P$4") (pinfunction "P$4_P$4") (pintype "bidirectional"))
      (node (ref "U10") (pin "3") (pinfunction "C(3)_3") (pintype "input"))
      (node (ref "U15") (pin "3") (pinfunction "C(3)_3") (pintype "input"))
      (node (ref "U19") (pin "3") (pinfunction "C(3)_3") (pintype "input"))
      (node (ref "U35") (pin "3") (pinfunction "C(3)_3") (pintype "input"))
    )
    (net (code "20") (name "GND") (class "Default")
      (node (ref "C10") (pin "P$1") (pinfunction "1_P$1") (pintype "passive"))
      (node (ref "C11") (pin "P$2") (pinfunction "2_P$2") (pintype "passive"))
      (node (ref "C13") (pin "P$1") (pinfunction "1_P$1") (pintype "passive"))
      (node (ref "C14") (pin "P$1") (pinfunction "1_P$1") (pintype "passive"))
      (node (ref "C15") (pin "2") (pinfunction "2_2") (pintype "passive"))
      (node (ref "C16") (pin "P$2") (pinfunction "2_P$2") (pintype "passive"))
      (node (ref "C30") (pin "P$1") (pinfunction "1_P$1") (pintype "passive"))
      (node (ref "C31") (pin "P$2") (pinfunction "2_P$2") (pintype "passive"))
      (node (ref "C32") (pin "P$2") (pinfunction "2_P$2") (pintype "passive"))
      (node (ref "C33") (pin "P$2") (pinfunction "2_P$2") (pintype "passive"))
      (node (ref "C34") (pin "P$2") (pinfunction "2_P$2") (pintype "passive"))
      (node (ref "C35") (pin "P$2") (pinfunction "2_P$2") (pintype "passive"))
      (node (ref "C36") (pin "P$1") (pinfunction "1_P$1") (pintype "passive"))
      (node (ref "C37") (pin "P$1") (pinfunction "1_P$1") (pintype "passive"))
      (node (ref "C38") (pin "P$2") (pinfunction "2_P$2") (pintype "passive"))
      (node (ref "C39") (pin "P$2") (pinfunction "2_P$2") (pintype "passive"))
      (node (ref "C40") (pin "P$2") (pinfunction "2_P$2") (pintype "passive"))
      (node (ref "C41") (pin "P$2") (pinfunction "2_P$2") (pintype "passive"))
      (node (ref "C42") (pin "P$2") (pinfunction "2_P$2") (pintype "passive"))
      (node (ref "C43") (pin "2") (pinfunction "2_2") (pintype "passive"))
      (node (ref "C44") (pin "P$2") (pinfunction "2_P$2") (pintype "passive"))
      (node (ref "C45") (pin "P$2") (pinfunction "2_P$2") (pintype "passive"))
      (node (ref "C46") (pin "P$2") (pinfunction "2_P$2") (pintype "passive"))
      (node (ref "C47") (pin "P$2") (pinfunction "2_P$2") (pintype "passive"))
      (node (ref "C48") (pin "2") (pinfunction "2_2") (pintype "passive"))
      (node (ref "C49") (pin "P$2") (pinfunction "2_P$2") (pintype "passive"))
      (node (ref "C5") (pin "P$2") (pinfunction "2_P$2") (pintype "passive"))
      (node (ref "C50") (pin "P$2") (pinfunction "2_P$2") (pintype "passive"))
      (node (ref "C51") (pin "P$2") (pinfunction "2_P$2") (pintype "passive"))
      (node (ref "C52") (pin "P$2") (pinfunction "2_P$2") (pintype "passive"))
      (node (ref "C53") (pin "P$2") (pinfunction "2_P$2") (pintype "passive"))
      (node (ref "C54") (pin "P$1") (pinfunction "1_P$1") (pintype "passive"))
      (node (ref "C55") (pin "P$1") (pinfunction "1_P$1") (pintype "passive"))
      (node (ref "C56") (pin "P$1") (pinfunction "1_P$1") (pintype "passive"))
      (node (ref "C57") (pin "P$2") (pinfunction "2_P$2") (pintype "passive"))
      (node (ref "C58") (pin "P$2") (pinfunction "2_P$2") (pintype "passive"))
      (node (ref "C59") (pin "P$2") (pinfunction "2_P$2") (pintype "passive"))
      (node (ref "C60") (pin "P$2") (pinfunction "2_P$2") (pintype "passive"))
      (node (ref "C61") (pin "P$1") (pinfunction "1_P$1") (pintype "passive"))
      (node (ref "C8") (pin "P$2") (pinfunction "2_P$2") (pintype "passive"))
      (node (ref "J1") (pin "1") (pinfunction "1_1") (pintype "passive"))
      (node (ref "J1") (pin "2") (pinfunction "2_2") (pintype "passive"))
      (node (ref "J11") (pin "10") (pinfunction "10_10") (pintype "passive"))
      (node (ref "J11") (pin "6") (pinfunction "6_6") (pintype "passive"))
      (node (ref "J11") (pin "8") (pinfunction "8_8") (pintype "passive"))
      (node (ref "J16") (pin "10") (pinfunction "10_10") (pintype "passive"))
      (node (ref "J16") (pin "2") (pinfunction "2_2") (pintype "passive"))
      (node (ref "J16") (pin "4") (pinfunction "4_4") (pintype "passive"))
      (node (ref "J16") (pin "6") (pinfunction "6_6") (pintype "passive"))
      (node (ref "J16") (pin "8") (pinfunction "8_8") (pintype "passive"))
      (node (ref "J2") (pin "P$5") (pinfunction "GND_P$5") (pintype "bidirectional"))
      (node (ref "J3") (pin "GND") (pinfunction "GND_GND") (pintype "power_in"))
      (node (ref "J4") (pin "10") (pinfunction "GLO_10") (pintype "bidirectional"))
      (node (ref "J4") (pin "8") (pinfunction "P8_8") (pintype "bidirectional"))
      (node (ref "J9") (pin "6") (pinfunction "SUPPLY_VOLTAGE_GROUND_6") (pintype "power_in"))
      (node (ref "LED3") (pin "C") (pinfunction "C_C") (pintype "passive"))
      (node (ref "R16") (pin "P$1") (pinfunction "1_P$1") (pintype "passive"))
      (node (ref "R17") (pin "P$1") (pinfunction "1_P$1") (pintype "passive"))
      (node (ref "R19") (pin "P$1") (pinfunction "1_P$1") (pintype "passive"))
      (node (ref "R25") (pin "P$1") (pinfunction "1_P$1") (pintype "passive"))
      (node (ref "R7") (pin "P$1") (pinfunction "1_P$1") (pintype "passive"))
      (node (ref "U$1") (pin "P$2") (pinfunction "2_P$2") (pintype "passive"))
      (node (ref "U$10") (pin "P$2") (pinfunction "2_P$2") (pintype "passive"))
      (node (ref "U$12") (pin "P$2") (pinfunction "2_P$2") (pintype "passive"))
      (node (ref "U$13") (pin "P$2") (pinfunction "2_P$2") (pintype "passive"))
      (node (ref "U$14") (pin "P$2") (pinfunction "2_P$2") (pintype "passive"))
      (node (ref "U$15") (pin "P$2") (pinfunction "2_P$2") (pintype "passive"))
      (node (ref "U$16") (pin "P$2") (pinfunction "2_P$2") (pintype "passive"))
      (node (ref "U$17") (pin "P$2") (pinfunction "2_P$2") (pintype "passive"))
      (node (ref "U$18") (pin "P$2") (pinfunction "2_P$2") (pintype "passive"))
      (node (ref "U$3") (pin "2") (pinfunction "2_2") (pintype "bidirectional"))
      (node (ref "U$3") (pin "4") (pinfunction "4_4") (pintype "bidirectional"))
      (node (ref "U$32") (pin "P$2") (pinfunction "2_P$2") (pintype "passive"))
      (node (ref "U$33") (pin "P$2") (pinfunction "2_P$2") (pintype "passive"))
      (node (ref "U$34") (pin "P$2") (pinfunction "2_P$2") (pintype "passive"))
      (node (ref "U$35") (pin "P$2") (pinfunction "2_P$2") (pintype "passive"))
      (node (ref "U$4") (pin "P$2") (pinfunction "2_P$2") (pintype "passive"))
      (node (ref "U$5") (pin "P$2") (pinfunction "2_P$2") (pintype "passive"))
      (node (ref "U$6") (pin "P$2") (pinfunction "2_P$2") (pintype "passive"))
      (node (ref "U$8") (pin "P$2") (pinfunction "2_P$2") (pintype "passive"))
      (node (ref "U10") (pin "2") (pinfunction "E(1)_2") (pintype "output"))
      (node (ref "U12") (pin "2") (pinfunction "E(1)_2") (pintype "output"))
      (node (ref "U13") (pin "2") (pinfunction "E(1)_2") (pintype "output"))
      (node (ref "U14") (pin "2") (pinfunction "E(1)_2") (pintype "output"))
      (node (ref "U15") (pin "2") (pinfunction "E(1)_2") (pintype "output"))
      (node (ref "U16") (pin "2") (pinfunction "E(1)_2") (pintype "output"))
      (node (ref "U17") (pin "2") (pinfunction "E(1)_2") (pintype "output"))
      (node (ref "U18") (pin "2") (pinfunction "E(1)_2") (pintype "output"))
      (node (ref "U19") (pin "2") (pinfunction "E(1)_2") (pintype "output"))
      (node (ref "U2") (pin "2") (pinfunction "GND_2") (pintype "input"))
      (node (ref "U3") (pin "22") (pinfunction "GND_22") (pintype "power_in"))
      (node (ref "U3") (pin "25") (pinfunction "25_25") (pintype "passive"))
      (node (ref "U32") (pin "2") (pinfunction "E(1)_2") (pintype "output"))
      (node (ref "U33") (pin "2") (pinfunction "E(1)_2") (pintype "output"))
      (node (ref "U34") (pin "2") (pinfunction "E(1)_2") (pintype "output"))
      (node (ref "U35") (pin "2") (pinfunction "E(1)_2") (pintype "output"))
      (node (ref "U4") (pin "111") (pinfunction "VSS(IO)5_111") (pintype "bidirectional"))
      (node (ref "U4") (pin "124") (pinfunction "VSS(IO)6_124") (pintype "bidirectional"))
      (node (ref "U4") (pin "139") (pinfunction "VSS(IO)7_139") (pintype "bidirectional"))
      (node (ref "U4") (pin "150") (pinfunction "VSS(IO)8_150") (pintype "bidirectional"))
      (node (ref "U4") (pin "156") (pinfunction "AVSS0_156") (pintype "bidirectional"))
      (node (ref "U4") (pin "170") (pinfunction "VSS(IO)9_170") (pintype "bidirectional"))
      (node (ref "U4") (pin "18") (pinfunction "VBAT_18") (pintype "bidirectional"))
      (node (ref "U4") (pin "22") (pinfunction "VSS1_22") (pintype "bidirectional"))
      (node (ref "U4") (pin "28") (pinfunction "AVSS_USBHS_28") (pintype "bidirectional"))
      (node (ref "U4") (pin "29") (pinfunction "PVSS_USBHS_29") (pintype "bidirectional"))
      (node (ref "U4") (pin "30") (pinfunction "VSS2_USBHS_30") (pintype "bidirectional"))
      (node (ref "U4") (pin "33") (pinfunction "VSS1_USBHS_33") (pintype "bidirectional"))
      (node (ref "U4") (pin "35") (pinfunction "VSSIO_35") (pintype "bidirectional"))
      (node (ref "U4") (pin "45") (pinfunction "VSS_USB_45") (pintype "bidirectional"))
      (node (ref "U4") (pin "60") (pinfunction "VSS(IO)2_60") (pintype "bidirectional"))
      (node (ref "U4") (pin "63") (pinfunction "VSS(IO/DCDC)_63") (pintype "bidirectional"))
      (node (ref "U4") (pin "66") (pinfunction "VCC_DCDC(IO/DCDC)_66") (pintype "bidirectional"))
      (node (ref "U4") (pin "83") (pinfunction "VSS(IO)3_83") (pintype "bidirectional"))
      (node (ref "U4") (pin "98") (pinfunction "VSS(IO)4_98") (pintype "bidirectional"))
      (node (ref "U7") (pin "2") (pinfunction "E(1)_2") (pintype "output"))
      (node (ref "U8") (pin "2") (pinfunction "E(1)_2") (pintype "output"))
      (node (ref "U9") (pin "2") (pinfunction "E(1)_2") (pintype "output"))
      (node (ref "X4") (pin "2") (pinfunction "2_2") (pintype "bidirectional"))
      (node (ref "X4") (pin "4") (pinfunction "4_4") (pintype "bidirectional"))
    )
    (net (code "21") (name "GNDE") (class "Default")
      (node (ref "J1") (pin "10") (pinfunction "10_10") (pintype "passive"))
      (node (ref "J1") (pin "9") (pinfunction "9_9") (pintype "passive"))
      (node (ref "J2") (pin "P$6") (pinfunction "SHIELD1_P$6") (pintype "bidirectional"))
      (node (ref "J2") (pin "P$7") (pinfunction "SHIELD2_P$7") (pintype "bidirectional"))
      (node (ref "J2") (pin "P$8") (pinfunction "SHIELD3_P$8") (pintype "bidirectional"))
      (node (ref "J2") (pin "P$9") (pinfunction "SHIELD4_P$9") (pintype "bidirectional"))
      (node (ref "J3") (pin "SHLD1") (pinfunction "SHIELD_1_SHLD1") (pintype "bidirectional"))
      (node (ref "J3") (pin "SHLD2") (pinfunction "SHIELD_2_SHLD2") (pintype "bidirectional"))
      (node (ref "J4") (pin "13") (pinfunction "GNDE0_13") (pintype "bidirectional"))
      (node (ref "J4") (pin "14") (pinfunction "GNDE1_14") (pintype "bidirectional"))
      (node (ref "J9") (pin "S1") (pinfunction "SHIELD_S1") (pintype "passive"))
      (node (ref "J9") (pin "S2") (pinfunction "SHIELD_S2") (pintype "passive"))
      (node (ref "J9") (pin "S3") (pinfunction "SHIELD_S3") (pintype "passive"))
      (node (ref "J9") (pin "S4") (pinfunction "SHIELD_S4") (pintype "passive"))
    )
    (net (code "22") (name "GP4") (class "Default")
      (node (ref "U4") (pin "49") (pinfunction "P2_7_49") (pintype "bidirectional"))
    )
    (net (code "23") (name "GP21") (class "Default")
      (node (ref "U4") (pin "73") (pinfunction "P9_5_73") (pintype "bidirectional"))
    )
    (net (code "24") (name "ID") (class "Default")
      (node (ref "J2") (pin "P$4") (pinfunction "ID_P$4") (pintype "bidirectional"))
    )
    (net (code "25") (name "IIC_0_SCL") (class "Default")
      (node (ref "J7") (pin "10") (pinfunction "10_10") (pintype "passive"))
      (node (ref "R11") (pin "P$2") (pinfunction "2_P$2") (pintype "passive"))
      (node (ref "U4") (pin "1") (pinfunction "P4_0_1") (pintype "bidirectional"))
    )
    (net (code "26") (name "IIC_0_SDA") (class "Default")
      (node (ref "J7") (pin "9") (pinfunction "9_9") (pintype "passive"))
      (node (ref "R14") (pin "P$2") (pinfunction "2_P$2") (pintype "passive"))
      (node (ref "U4") (pin "2") (pinfunction "P4_1_2") (pintype "bidirectional"))
    )
    (net (code "27") (name "IIC_1_SCL") (class "Default")
      (node (ref "J10") (pin "P$5") (pinfunction "P$5_P$5") (pintype "bidirectional"))
      (node (ref "R20") (pin "P$2") (pinfunction "2_P$2") (pintype "passive"))
      (node (ref "U4") (pin "132") (pinfunction "P1_0_132") (pintype "bidirectional"))
    )
    (net (code "28") (name "IIC_1_SDA") (class "Default")
      (node (ref "J10") (pin "P$6") (pinfunction "P$6_P$6") (pintype "bidirectional"))
      (node (ref "R21") (pin "P$2") (pinfunction "2_P$2") (pintype "passive"))
      (node (ref "U4") (pin "131") (pinfunction "P1_1_131") (pintype "bidirectional"))
    )
    (net (code "29") (name "INT_AI_LS_0") (class "Default")
      (node (ref "J15") (pin "P$1") (pinfunction "P$1_P$1") (pintype "bidirectional"))
      (node (ref "U4") (pin "3") (pinfunction "P4_2_3") (pintype "bidirectional"))
    )
    (net (code "30") (name "INT_AI_LS_1") (class "Default")
      (node (ref "J15") (pin "P$2") (pinfunction "P$2_P$2") (pintype "bidirectional"))
      (node (ref "U4") (pin "43") (pinfunction "P4_8_43") (pintype "bidirectional"))
    )
    (net (code "31") (name "INT_AI_LS_2") (class "Default")
      (node (ref "J15") (pin "P$3") (pinfunction "P$3_P$3") (pintype "bidirectional"))
      (node (ref "U4") (pin "53") (pinfunction "P2_3_53") (pintype "bidirectional"))
    )
    (net (code "32") (name "INT_AI_LS_3") (class "Default")
      (node (ref "J15") (pin "P$4") (pinfunction "P$4_P$4") (pintype "bidirectional"))
      (node (ref "U4") (pin "54") (pinfunction "P2_2_54") (pintype "bidirectional"))
    )
    (net (code "33") (name "INT_MI_01") (class "Default")
      (node (ref "J10") (pin "P$39") (pinfunction "P$39_P$39") (pintype "bidirectional"))
      (node (ref "U4") (pin "87") (pinfunction "P3_1_87") (pintype "bidirectional"))
    )
    (net (code "34") (name "INT_MI_02") (class "Default")
      (node (ref "J10") (pin "P$40") (pinfunction "P$40_P$40") (pintype "bidirectional"))
      (node (ref "U4") (pin "86") (pinfunction "P3_2_86") (pintype "bidirectional"))
    )
    (net (code "35") (name "INT_MI_03") (class "Default")
      (node (ref "J10") (pin "P$9") (pinfunction "P$9_P$9") (pintype "bidirectional"))
      (node (ref "U4") (pin "128") (pinfunction "P1_4_128") (pintype "bidirectional"))
    )
    (net (code "36") (name "INT_MI_04") (class "Default")
      (node (ref "J10") (pin "P$10") (pinfunction "P$10_P$10") (pintype "bidirectional"))
      (node (ref "U4") (pin "127") (pinfunction "P1_5_127") (pintype "bidirectional"))
    )
    (net (code "37") (name "INT_MI_05") (class "Default")
      (node (ref "J10") (pin "P$1") (pinfunction "P$1_P$1") (pintype "bidirectional"))
    )
    (net (code "38") (name "LED1{slash}SPEED") (class "Default")
      (node (ref "J4") (pin "11") (pinfunction "YLO_11") (pintype "bidirectional"))
      (node (ref "U3") (pin "23") (pinfunction "LED0/ANEN_SPEED_23") (pintype "bidirectional"))
    )
    (net (code "39") (name "M0_DIR") (class "Default")
      (node (ref "RXS4") (pin "P$1") (pinfunction "1_P$1") (pintype "passive"))
      (node (ref "U4") (pin "39") (pinfunction "P4_12_39") (pintype "bidirectional"))
    )
    (net (code "40") (name "M0_STEP") (class "Default")
      (node (ref "RXS2") (pin "P$1") (pinfunction "1_P$1") (pintype "passive"))
      (node (ref "U4") (pin "16") (pinfunction "PB_0_16") (pintype "bidirectional"))
    )
    (net (code "41") (name "M1_DIR") (class "Default")
      (node (ref "RYS7") (pin "P$1") (pinfunction "1_P$1") (pintype "passive"))
      (node (ref "U4") (pin "40") (pinfunction "P4_11_40") (pintype "bidirectional"))
    )
    (net (code "42") (name "M1_STEP") (class "Default")
      (node (ref "RYS3") (pin "P$1") (pinfunction "1_P$1") (pintype "passive"))
      (node (ref "U4") (pin "36") (pinfunction "P4_15_36") (pintype "bidirectional"))
    )
    (net (code "43") (name "M2_DIR") (class "Default")
      (node (ref "RZS4") (pin "P$1") (pinfunction "1_P$1") (pintype "passive"))
      (node (ref "U4") (pin "41") (pinfunction "P4_10_41") (pintype "bidirectional"))
    )
    (net (code "44") (name "M2_STEP") (class "Default")
      (node (ref "RZS2") (pin "P$1") (pinfunction "1_P$1") (pintype "passive"))
      (node (ref "U4") (pin "37") (pinfunction "P4_14_37") (pintype "bidirectional"))
    )
    (net (code "45") (name "M3_DIR") (class "Default")
      (node (ref "RYS8") (pin "P$1") (pinfunction "1_P$1") (pintype "passive"))
      (node (ref "U4") (pin "42") (pinfunction "P4_9_42") (pintype "bidirectional"))
    )
    (net (code "46") (name "M3_STEP") (class "Default")
      (node (ref "RYS4") (pin "P$1") (pinfunction "1_P$1") (pintype "passive"))
      (node (ref "U4") (pin "38") (pinfunction "P4_13_38") (pintype "bidirectional"))
    )
    (net (code "47") (name "NC") (class "Default")
      (node (ref "J4") (pin "7") (pinfunction "P7_7") (pintype "bidirectional"))
    )
    (net (code "48") (name "Net-(C16-1)") (class "Default")
      (node (ref "C16") (pin "P$1") (pinfunction "1_P$1") (pintype "passive"))
      (node (ref "J2") (pin "P$1") (pinfunction "VBUS_P$1") (pintype "bidirectional"))
      (node (ref "R4") (pin "P$2") (pinfunction "2_P$2") (pintype "passive"))
      (node (ref "R7") (pin "P$2") (pinfunction "2_P$2") (pintype "passive"))
    )
    (net (code "49") (name "Net-(C31-1)") (class "Default")
      (node (ref "C31") (pin "P$1") (pinfunction "1_P$1") (pintype "passive"))
      (node (ref "U4") (pin "62") (pinfunction "VCL1_62") (pintype "bidirectional"))
    )
    (net (code "50") (name "Net-(C37-2)") (class "Default")
      (node (ref "C37") (pin "P$2") (pinfunction "2_P$2") (pintype "passive"))
      (node (ref "U4") (pin "148") (pinfunction "VCL2_148") (pintype "bidirectional"))
    )
    (net (code "51") (name "Net-(C38-1)") (class "Default")
      (node (ref "C38") (pin "P$1") (pinfunction "1_P$1") (pintype "passive"))
      (node (ref "U4") (pin "19") (pinfunction "VCLO_19") (pintype "bidirectional"))
    )
    (net (code "52") (name "Net-(C44-1)") (class "Default")
      (node (ref "C43") (pin "1") (pinfunction "1_1") (pintype "passive"))
      (node (ref "C44") (pin "P$1") (pinfunction "1_P$1") (pintype "passive"))
      (node (ref "FB2/2") (pin "2") (pinfunction "P$2_2") (pintype "bidirectional"))
      (node (ref "U3") (pin "2") (pinfunction "VDDA_3.3_2") (pintype "power_in"))
    )
    (net (code "53") (name "Net-(J2-D+)") (class "Default")
      (node (ref "J2") (pin "P$3") (pinfunction "D+_P$3") (pintype "bidirectional"))
      (node (ref "R6") (pin "P$2") (pinfunction "2_P$2") (pintype "passive"))
    )
    (net (code "54") (name "Net-(J2-D-)") (class "Default")
      (node (ref "J2") (pin "P$2") (pinfunction "D-_P$2") (pintype "bidirectional"))
      (node (ref "R5") (pin "P$2") (pinfunction "2_P$2") (pintype "passive"))
    )
    (net (code "55") (name "Net-(R13-1)") (class "Default")
      (node (ref "LED3") (pin "A") (pinfunction "A_A") (pintype "passive"))
      (node (ref "R13") (pin "P$1") (pinfunction "1_P$1") (pintype "passive"))
    )
    (net (code "56") (name "Net-(R16-2)") (class "Default")
      (node (ref "R16") (pin "P$2") (pinfunction "2_P$2") (pintype "passive"))
      (node (ref "U4") (pin "65") (pinfunction "VLO2(DCDC)_65") (pintype "bidirectional"))
    )
    (net (code "57") (name "Net-(R17-2)") (class "Default")
      (node (ref "R17") (pin "P$2") (pinfunction "2_P$2") (pintype "passive"))
      (node (ref "U4") (pin "64") (pinfunction "VLO1(DCDC)_64") (pintype "bidirectional"))
    )
    (net (code "58") (name "Net-(R19-2)") (class "Default")
      (node (ref "R19") (pin "P$2") (pinfunction "2_P$2") (pintype "passive"))
      (node (ref "U4") (pin "27") (pinfunction "USBHS_RREF_27") (pintype "bidirectional"))
    )
    (net (code "59") (name "Net-(RXS2-2)") (class "Default")
      (node (ref "RXS2") (pin "P$2") (pinfunction "2_P$2") (pintype "passive"))
      (node (ref "U$5") (pin "P$1") (pinfunction "1_P$1") (pintype "passive"))
      (node (ref "U8") (pin "1") (pinfunction "B(2)_1") (pintype "input"))
    )
    (net (code "60") (name "Net-(RXS3-2)") (class "Default")
      (node (ref "RXS3") (pin "P$2") (pinfunction "2_P$2") (pintype "passive"))
      (node (ref "U$12") (pin "P$1") (pinfunction "1_P$1") (pintype "passive"))
      (node (ref "U13") (pin "1") (pinfunction "B(2)_1") (pintype "input"))
    )
    (net (code "61") (name "Net-(RXS4-2)") (class "Default")
      (node (ref "RXS4") (pin "P$2") (pinfunction "2_P$2") (pintype "passive"))
      (node (ref "U$16") (pin "P$1") (pinfunction "1_P$1") (pintype "passive"))
      (node (ref "U17") (pin "1") (pinfunction "B(2)_1") (pintype "input"))
    )
    (net (code "62") (name "Net-(RXS8-2)") (class "Default")
      (node (ref "RXS8") (pin "P$2") (pinfunction "2_P$2") (pintype "passive"))
      (node (ref "U$33") (pin "P$1") (pinfunction "1_P$1") (pintype "passive"))
      (node (ref "U33") (pin "1") (pinfunction "B(2)_1") (pintype "input"))
    )
    (net (code "63") (name "Net-(RYS3-2)") (class "Default")
      (node (ref "RYS3") (pin "P$2") (pinfunction "2_P$2") (pintype "passive"))
      (node (ref "U$6") (pin "P$1") (pinfunction "1_P$1") (pintype "passive"))
      (node (ref "U9") (pin "1") (pinfunction "B(2)_1") (pintype "input"))
    )
    (net (code "64") (name "Net-(RYS4-2)") (class "Default")
      (node (ref "RYS4") (pin "P$2") (pinfunction "2_P$2") (pintype "passive"))
      (node (ref "U$8") (pin "P$1") (pinfunction "1_P$1") (pintype "passive"))
      (node (ref "U10") (pin "1") (pinfunction "B(2)_1") (pintype "input"))
    )
    (net (code "65") (name "Net-(RYS5-2)") (class "Default")
      (node (ref "RYS5") (pin "P$2") (pinfunction "2_P$2") (pintype "passive"))
      (node (ref "U$13") (pin "P$1") (pinfunction "1_P$1") (pintype "passive"))
      (node (ref "U14") (pin "1") (pinfunction "B(2)_1") (pintype "input"))
    )
    (net (code "66") (name "Net-(RYS6-2)") (class "Default")
      (node (ref "RYS6") (pin "P$2") (pinfunction "2_P$2") (pintype "passive"))
      (node (ref "U$14") (pin "P$1") (pinfunction "1_P$1") (pintype "passive"))
      (node (ref "U15") (pin "1") (pinfunction "B(2)_1") (pintype "input"))
    )
    (net (code "67") (name "Net-(RYS7-2)") (class "Default")
      (node (ref "RYS7") (pin "P$2") (pinfunction "2_P$2") (pintype "passive"))
      (node (ref "U$17") (pin "P$1") (pinfunction "1_P$1") (pintype "passive"))
      (node (ref "U18") (pin "1") (pinfunction "B(2)_1") (pintype "input"))
    )
    (net (code "68") (name "Net-(RYS8-2)") (class "Default")
      (node (ref "RYS8") (pin "P$2") (pinfunction "2_P$2") (pintype "passive"))
      (node (ref "U$18") (pin "P$1") (pinfunction "1_P$1") (pintype "passive"))
      (node (ref "U19") (pin "1") (pinfunction "B(2)_1") (pintype "input"))
    )
    (net (code "69") (name "Net-(RYS15-2)") (class "Default")
      (node (ref "RYS15") (pin "P$2") (pinfunction "2_P$2") (pintype "passive"))
      (node (ref "U$34") (pin "P$1") (pinfunction "1_P$1") (pintype "passive"))
      (node (ref "U34") (pin "1") (pinfunction "B(2)_1") (pintype "input"))
    )
    (net (code "70") (name "Net-(RYS16-2)") (class "Default")
      (node (ref "RYS16") (pin "P$2") (pinfunction "2_P$2") (pintype "passive"))
      (node (ref "U$35") (pin "P$1") (pinfunction "1_P$1") (pintype "passive"))
      (node (ref "U35") (pin "1") (pinfunction "B(2)_1") (pintype "input"))
    )
    (net (code "71") (name "Net-(RZS2-2)") (class "Default")
      (node (ref "RZS2") (pin "P$2") (pinfunction "2_P$2") (pintype "passive"))
      (node (ref "U$1") (pin "P$1") (pinfunction "1_P$1") (pintype "passive"))
      (node (ref "U7") (pin "1") (pinfunction "B(2)_1") (pintype "input"))
    )
    (net (code "72") (name "Net-(RZS3-2)") (class "Default")
      (node (ref "RZS3") (pin "P$2") (pinfunction "2_P$2") (pintype "passive"))
      (node (ref "U$10") (pin "P$1") (pinfunction "1_P$1") (pintype "passive"))
      (node (ref "U12") (pin "1") (pinfunction "B(2)_1") (pintype "input"))
    )
    (net (code "73") (name "Net-(RZS4-2)") (class "Default")
      (node (ref "RZS4") (pin "P$2") (pinfunction "2_P$2") (pintype "passive"))
      (node (ref "U$15") (pin "P$1") (pinfunction "1_P$1") (pintype "passive"))
      (node (ref "U16") (pin "1") (pinfunction "B(2)_1") (pintype "input"))
    )
    (net (code "74") (name "Net-(RZS8-2)") (class "Default")
      (node (ref "RZS8") (pin "P$2") (pinfunction "2_P$2") (pintype "passive"))
      (node (ref "U$32") (pin "P$1") (pinfunction "1_P$1") (pintype "passive"))
      (node (ref "U32") (pin "1") (pinfunction "B(2)_1") (pintype "input"))
    )
    (net (code "75") (name "P0_00") (class "Default")
      (node (ref "J7") (pin "3") (pinfunction "3_3") (pintype "passive"))
      (node (ref "U4") (pin "169") (pinfunction "P0_0/AN0\\00_169") (pintype "bidirectional"))
    )
    (net (code "76") (name "P0_01") (class "Default")
      (node (ref "J7") (pin "4") (pinfunction "4_4") (pintype "passive"))
      (node (ref "U4") (pin "168") (pinfunction "P0_1/AN001_168") (pintype "bidirectional"))
    )
    (net (code "77") (name "P0_02") (class "Default")
      (node (ref "J7") (pin "1") (pinfunction "1_1") (pintype "passive"))
      (node (ref "U4") (pin "167") (pinfunction "P0_2/AN002_167") (pintype "bidirectional"))
    )
    (net (code "78") (name "P0_03") (class "Default")
      (node (ref "J7") (pin "2") (pinfunction "2_2") (pintype "passive"))
      (node (ref "U4") (pin "166") (pinfunction "P0_3/PGAVSS000_166") (pintype "bidirectional"))
    )
    (net (code "79") (name "P0_04") (class "Default")
      (node (ref "J8") (pin "9") (pinfunction "9_9") (pintype "passive"))
      (node (ref "U4") (pin "165") (pinfunction "P0_4/AN100_165") (pintype "bidirectional"))
    )
    (net (code "80") (name "P0_05") (class "Default")
      (node (ref "J8") (pin "10") (pinfunction "10_10") (pintype "passive"))
      (node (ref "U4") (pin "164") (pinfunction "P0_5/AN101_164") (pintype "bidirectional"))
    )
    (net (code "81") (name "P0_06") (class "Default")
      (node (ref "J8") (pin "7") (pinfunction "7_7") (pintype "passive"))
      (node (ref "U4") (pin "163") (pinfunction "P0_6/AN102_163") (pintype "bidirectional"))
    )
    (net (code "82") (name "P0_07") (class "Default")
      (node (ref "J8") (pin "8") (pinfunction "8_8") (pintype "passive"))
      (node (ref "U4") (pin "162") (pinfunction "P0_7/PGVSS100_162") (pintype "bidirectional"))
    )
    (net (code "83") (name "P0_08") (class "Default")
      (node (ref "J8") (pin "5") (pinfunction "5_5") (pintype "passive"))
      (node (ref "U4") (pin "161") (pinfunction "P0_8/AN003_161") (pintype "bidirectional"))
    )
    (net (code "84") (name "P0_09") (class "Default")
      (node (ref "J8") (pin "6") (pinfunction "6_6") (pintype "passive"))
      (node (ref "U4") (pin "160") (pinfunction "P0_9/AN004_160") (pintype "bidirectional"))
    )
    (net (code "85") (name "P0_14") (class "Default")
      (node (ref "J8") (pin "3") (pinfunction "3_3") (pintype "passive"))
      (node (ref "U4") (pin "152") (pinfunction "P0_14/DA0/AN005/AN105_152") (pintype "bidirectional"))
    )
    (net (code "86") (name "P0_15") (class "Default")
      (node (ref "J8") (pin "4") (pinfunction "4_4") (pintype "passive"))
      (node (ref "U4") (pin "151") (pinfunction "P0_15/DA1/AN006/AN106_151") (pintype "bidirectional"))
    )
    (net (code "87") (name "P1_02") (class "Default")
      (node (ref "J10") (pin "P$7") (pinfunction "P$7_P$7") (pintype "bidirectional"))
      (node (ref "U4") (pin "130") (pinfunction "P1_2_130") (pintype "bidirectional"))
    )
    (net (code "88") (name "P1_03") (class "Default")
      (node (ref "J10") (pin "P$8") (pinfunction "P$8_P$8") (pintype "bidirectional"))
      (node (ref "U4") (pin "129") (pinfunction "P1_3_129") (pintype "bidirectional"))
    )
    (net (code "89") (name "P1_06") (class "Default")
      (node (ref "J10") (pin "P$11") (pinfunction "P$11_P$11") (pintype "bidirectional"))
      (node (ref "U4") (pin "126") (pinfunction "P1_6_126") (pintype "bidirectional"))
    )
    (net (code "90") (name "P1_07") (class "Default")
      (node (ref "J10") (pin "P$12") (pinfunction "P$12_P$12") (pintype "bidirectional"))
      (node (ref "U4") (pin "125") (pinfunction "P1_7_125") (pintype "bidirectional"))
    )
    (net (code "91") (name "P1_11") (class "Default")
      (node (ref "J10") (pin "P$38") (pinfunction "P$38_P$38") (pintype "bidirectional"))
      (node (ref "U4") (pin "92") (pinfunction "P1_11_92") (pintype "bidirectional"))
    )
    (net (code "92") (name "P1_12") (class "Default")
      (node (ref "J10") (pin "P$37") (pinfunction "P$37_P$37") (pintype "bidirectional"))
      (node (ref "U4") (pin "93") (pinfunction "P1_12_93") (pintype "bidirectional"))
    )
    (net (code "93") (name "P1_13") (class "Default")
      (node (ref "J10") (pin "P$36") (pinfunction "P$36_P$36") (pintype "bidirectional"))
      (node (ref "U4") (pin "94") (pinfunction "P1_13_94") (pintype "bidirectional"))
    )
    (net (code "94") (name "P1_14") (class "Default")
      (node (ref "J10") (pin "P$35") (pinfunction "P$35_P$35") (pintype "bidirectional"))
      (node (ref "U4") (pin "95") (pinfunction "P1_14_95") (pintype "bidirectional"))
    )
    (net (code "95") (name "P1_15") (class "Default")
      (node (ref "J10") (pin "P$34") (pinfunction "P$34_P$34") (pintype "bidirectional"))
      (node (ref "U4") (pin "96") (pinfunction "P1_15_96") (pintype "bidirectional"))
    )
    (net (code "96") (name "P2_00") (class "Default")
      (node (ref "J16") (pin "3") (pinfunction "3_3") (pintype "passive"))
      (node (ref "R3") (pin "P$2") (pinfunction "2_P$2") (pintype "passive"))
      (node (ref "U4") (pin "69") (pinfunction "P2_0(INPUT_ONLY)_69") (pintype "bidirectional"))
    )
    (net (code "97") (name "P2_01") (class "Default")
      (node (ref "J16") (pin "1") (pinfunction "1_1") (pintype "passive"))
      (node (ref "R2") (pin "P$2") (pinfunction "2_P$2") (pintype "passive"))
      (node (ref "U4") (pin "68") (pinfunction "P2_1/MD_68") (pintype "bidirectional"))
    )
    (net (code "98") (name "P3_03") (class "Default")
      (node (ref "J12") (pin "1") (pinfunction "1_1") (pintype "passive"))
      (node (ref "U4") (pin "85") (pinfunction "P3_3_85") (pintype "bidirectional"))
    )
    (net (code "99") (name "P3_04") (class "Default")
      (node (ref "J12") (pin "2") (pinfunction "2_2") (pintype "passive"))
      (node (ref "U4") (pin "82") (pinfunction "P3_4_82") (pintype "bidirectional"))
    )
    (net (code "100") (name "P3_05") (class "Default")
      (node (ref "J12") (pin "3") (pinfunction "3_3") (pintype "passive"))
      (node (ref "U4") (pin "81") (pinfunction "P3_5_81") (pintype "bidirectional"))
    )
    (net (code "101") (name "P3_06") (class "Default")
      (node (ref "J12") (pin "4") (pinfunction "4_4") (pintype "passive"))
      (node (ref "U4") (pin "80") (pinfunction "P3_6_80") (pintype "bidirectional"))
    )
    (net (code "102") (name "P3_07") (class "Default")
      (node (ref "J12") (pin "5") (pinfunction "5_5") (pintype "passive"))
      (node (ref "U4") (pin "79") (pinfunction "P3_7_79") (pintype "bidirectional"))
    )
    (net (code "103") (name "P3_09") (class "Default")
      (node (ref "J12") (pin "6") (pinfunction "6_6") (pintype "passive"))
      (node (ref "U4") (pin "77") (pinfunction "P3_9_77") (pintype "bidirectional"))
    )
    (net (code "104") (name "P3_10") (class "Default")
      (node (ref "J12") (pin "7") (pinfunction "7_7") (pintype "passive"))
      (node (ref "U4") (pin "76") (pinfunction "P3_10_76") (pintype "bidirectional"))
    )
    (net (code "105") (name "P3_11") (class "Default")
      (node (ref "J12") (pin "8") (pinfunction "8_8") (pintype "passive"))
      (node (ref "U4") (pin "75") (pinfunction "P3_11_75") (pintype "bidirectional"))
    )
    (net (code "106") (name "P3_12") (class "Default")
      (node (ref "J12") (pin "9") (pinfunction "9_9") (pintype "passive"))
      (node (ref "U4") (pin "74") (pinfunction "P3_12_74") (pintype "bidirectional"))
    )
    (net (code "107") (name "P5_11") (class "Default")
      (node (ref "J7") (pin "7") (pinfunction "7_7") (pintype "passive"))
      (node (ref "U4") (pin "176") (pinfunction "P5_11_176") (pintype "bidirectional"))
    )
    (net (code "108") (name "P5_12") (class "Default")
      (node (ref "J7") (pin "8") (pinfunction "8_8") (pintype "passive"))
      (node (ref "U4") (pin "175") (pinfunction "P5_12_175") (pintype "bidirectional"))
    )
    (net (code "109") (name "P5_13") (class "Default")
      (node (ref "J7") (pin "5") (pinfunction "5_5") (pintype "passive"))
      (node (ref "U4") (pin "174") (pinfunction "P5_13_174") (pintype "bidirectional"))
    )
    (net (code "110") (name "P6_00") (class "Default")
      (node (ref "J10") (pin "P$13") (pinfunction "P$13_P$13") (pintype "bidirectional"))
      (node (ref "U4") (pin "122") (pinfunction "P6_0_122") (pintype "bidirectional"))
    )
    (net (code "111") (name "P6_01") (class "Default")
      (node (ref "J10") (pin "P$14") (pinfunction "P$14_P$14") (pintype "bidirectional"))
      (node (ref "U4") (pin "121") (pinfunction "P6_1_121") (pintype "bidirectional"))
    )
    (net (code "112") (name "P6_02") (class "Default")
      (node (ref "J10") (pin "P$15") (pinfunction "P$15_P$15") (pintype "bidirectional"))
      (node (ref "U4") (pin "120") (pinfunction "P6_2_120") (pintype "bidirectional"))
    )
    (net (code "113") (name "P6_03") (class "Default")
      (node (ref "J10") (pin "P$16") (pinfunction "P$16_P$16") (pintype "bidirectional"))
      (node (ref "U4") (pin "119") (pinfunction "P6_3_119") (pintype "bidirectional"))
    )
    (net (code "114") (name "P6_04") (class "Default")
      (node (ref "J10") (pin "P$17") (pinfunction "P$17_P$17") (pintype "bidirectional"))
      (node (ref "U4") (pin "118") (pinfunction "P6_4_118") (pintype "bidirectional"))
    )
    (net (code "115") (name "P6_05") (class "Default")
      (node (ref "J10") (pin "P$18") (pinfunction "P$18_P$18") (pintype "bidirectional"))
      (node (ref "U4") (pin "117") (pinfunction "P6_5_117") (pintype "bidirectional"))
    )
    (net (code "116") (name "P6_06") (class "Default")
      (node (ref "J10") (pin "P$19") (pinfunction "P$19_P$19") (pintype "bidirectional"))
      (node (ref "U4") (pin "116") (pinfunction "P6_6_116") (pintype "bidirectional"))
    )
    (net (code "117") (name "P6_07") (class "Default")
      (node (ref "J10") (pin "P$20") (pinfunction "P$20_P$20") (pintype "bidirectional"))
      (node (ref "U4") (pin "115") (pinfunction "P6_7_115") (pintype "bidirectional"))
    )
    (net (code "118") (name "P6_08") (class "Default")
      (node (ref "J10") (pin "P$33") (pinfunction "P$33_P$33") (pintype "bidirectional"))
      (node (ref "U4") (pin "99") (pinfunction "P6_8_99") (pintype "bidirectional"))
    )
    (net (code "119") (name "P6_09") (class "Default")
      (node (ref "J10") (pin "P$32") (pinfunction "P$32_P$32") (pintype "bidirectional"))
      (node (ref "U4") (pin "100") (pinfunction "P6_9_100") (pintype "bidirectional"))
    )
    (net (code "120") (name "P6_10") (class "Default")
      (node (ref "J10") (pin "P$31") (pinfunction "P$31_P$31") (pintype "bidirectional"))
      (node (ref "U4") (pin "101") (pinfunction "P6_10_101") (pintype "bidirectional"))
    )
    (net (code "121") (name "P6_11") (class "Default")
      (node (ref "J10") (pin "P$30") (pinfunction "P$30_P$30") (pintype "bidirectional"))
      (node (ref "U4") (pin "102") (pinfunction "P6_11_102") (pintype "bidirectional"))
    )
    (net (code "122") (name "P6_12") (class "Default")
      (node (ref "J10") (pin "P$29") (pinfunction "P$29_P$29") (pintype "bidirectional"))
      (node (ref "U4") (pin "103") (pinfunction "P6_12_103") (pintype "bidirectional"))
    )
    (net (code "123") (name "P6_13") (class "Default")
      (node (ref "J10") (pin "P$28") (pinfunction "P$28_P$28") (pintype "bidirectional"))
      (node (ref "U4") (pin "104") (pinfunction "P6_13_104") (pintype "bidirectional"))
    )
    (net (code "124") (name "P6_14") (class "Default")
      (node (ref "J10") (pin "P$27") (pinfunction "P$27_P$27") (pintype "bidirectional"))
      (node (ref "U4") (pin "105") (pinfunction "P6_14_105") (pintype "bidirectional"))
    )
    (net (code "125") (name "P6_15") (class "Default")
      (node (ref "J10") (pin "P$26") (pinfunction "P$26_P$26") (pintype "bidirectional"))
      (node (ref "U4") (pin "106") (pinfunction "P6_15_106") (pintype "bidirectional"))
    )
    (net (code "126") (name "P7_06") (class "Default")
      (node (ref "U4") (pin "14") (pinfunction "P7_6_14") (pintype "bidirectional"))
    )
    (net (code "127") (name "P7_07") (class "Default")
      (node (ref "U4") (pin "15") (pinfunction "P7_7_15") (pintype "bidirectional"))
    )
    (net (code "128") (name "P8_00") (class "Default")
      (node (ref "J10") (pin "P$4") (pinfunction "P$4_P$4") (pintype "bidirectional"))
      (node (ref "U4") (pin "133") (pinfunction "P8_0_133") (pintype "bidirectional"))
    )
    (net (code "129") (name "P8_01") (class "Default")
      (node (ref "J10") (pin "P$3") (pinfunction "P$3_P$3") (pintype "bidirectional"))
      (node (ref "U4") (pin "134") (pinfunction "P8_1_134") (pintype "bidirectional"))
    )
    (net (code "130") (name "P8_02") (class "Default")
      (node (ref "J10") (pin "P$2") (pinfunction "P$2_P$2") (pintype "bidirectional"))
      (node (ref "U4") (pin "135") (pinfunction "P8_2_135") (pintype "bidirectional"))
    )
    (net (code "131") (name "P8_03") (class "Default")
      (node (ref "J8") (pin "2") (pinfunction "2_2") (pintype "passive"))
      (node (ref "U4") (pin "136") (pinfunction "P8_3_136") (pintype "bidirectional"))
    )
    (net (code "132") (name "P8_04") (class "Default")
      (node (ref "J8") (pin "1") (pinfunction "1_1") (pintype "passive"))
      (node (ref "U4") (pin "137") (pinfunction "P8_4_137") (pintype "bidirectional"))
    )
    (net (code "133") (name "P8_05") (class "Default")
      (node (ref "J7") (pin "6") (pinfunction "6_6") (pintype "passive"))
      (node (ref "U4") (pin "173") (pinfunction "P8_5_173") (pintype "bidirectional"))
    )
    (net (code "134") (name "P9_05") (class "Default")
      (node (ref "J12") (pin "10") (pinfunction "10_10") (pintype "passive"))
    )
    (net (code "135") (name "P9_06") (class "Default")
      (node (ref "J16") (pin "9") (pinfunction "9_9") (pintype "passive"))
      (node (ref "R10") (pin "P$2") (pinfunction "2_P$2") (pintype "passive"))
      (node (ref "U4") (pin "72") (pinfunction "P9_6_72") (pintype "bidirectional"))
    )
    (net (code "136") (name "P9_07") (class "Default")
      (node (ref "J16") (pin "7") (pinfunction "7_7") (pintype "passive"))
      (node (ref "R9") (pin "P$2") (pinfunction "2_P$2") (pintype "passive"))
      (node (ref "U4") (pin "71") (pinfunction "P9_7_71") (pintype "bidirectional"))
    )
    (net (code "137") (name "P9_08") (class "Default")
      (node (ref "J16") (pin "5") (pinfunction "5_5") (pintype "passive"))
      (node (ref "R8") (pin "P$2") (pinfunction "2_P$2") (pintype "passive"))
      (node (ref "U4") (pin "70") (pinfunction "P9_8_70") (pintype "bidirectional"))
    )
    (net (code "138") (name "PA_00") (class "Default")
      (node (ref "J10") (pin "P$21") (pinfunction "P$21_P$21") (pintype "bidirectional"))
      (node (ref "U4") (pin "114") (pinfunction "PA_0_114") (pintype "bidirectional"))
    )
    (net (code "139") (name "PA_01") (class "Default")
      (node (ref "J10") (pin "P$22") (pinfunction "P$22_P$22") (pintype "bidirectional"))
      (node (ref "U4") (pin "113") (pinfunction "PA_1_113") (pintype "bidirectional"))
    )
    (net (code "140") (name "PA_08") (class "Default")
      (node (ref "J10") (pin "P$25") (pinfunction "P$25_P$25") (pintype "bidirectional"))
      (node (ref "U4") (pin "107") (pinfunction "PA_8_107") (pintype "bidirectional"))
    )
    (net (code "141") (name "PA_09") (class "Default")
      (node (ref "J10") (pin "P$24") (pinfunction "P$24_P$24") (pintype "bidirectional"))
      (node (ref "U4") (pin "108") (pinfunction "PA_9_108") (pintype "bidirectional"))
    )
    (net (code "142") (name "PA_10") (class "Default")
      (node (ref "J10") (pin "P$23") (pinfunction "P$23_P$23") (pintype "bidirectional"))
      (node (ref "U4") (pin "109") (pinfunction "PA_10_109") (pintype "bidirectional"))
    )
    (net (code "143") (name "R51") (class "Default")
      (node (ref "J4") (pin "12") (pinfunction "YHI_12") (pintype "bidirectional"))
      (node (ref "R23") (pin "P$1") (pinfunction "1_P$1") (pintype "passive"))
    )
    (net (code "144") (name "R52") (class "Default")
      (node (ref "J4") (pin "9") (pinfunction "GHI_9") (pintype "bidirectional"))
      (node (ref "R24") (pin "P$1") (pinfunction "1_P$1") (pintype "passive"))
    )
    (net (code "145") (name "RELAY_0") (class "Default")
      (node (ref "RYS6") (pin "P$1") (pinfunction "1_P$1") (pintype "passive"))
      (node (ref "U4") (pin "59") (pinfunction "P9_1_59") (pintype "bidirectional"))
    )
    (net (code "146") (name "RELAY_1") (class "Default")
      (node (ref "RZS3") (pin "P$1") (pinfunction "1_P$1") (pintype "passive"))
      (node (ref "U4") (pin "58") (pinfunction "P9_0_58") (pintype "bidirectional"))
    )
    (net (code "147") (name "RELAY_2") (class "Default")
      (node (ref "RYS5") (pin "P$1") (pinfunction "1_P$1") (pintype "passive"))
      (node (ref "U4") (pin "57") (pinfunction "P3_15_57") (pintype "bidirectional"))
    )
    (net (code "148") (name "RELAY_3") (class "Default")
      (node (ref "RXS3") (pin "P$1") (pinfunction "1_P$1") (pintype "passive"))
      (node (ref "U4") (pin "56") (pinfunction "P3_14_56") (pintype "bidirectional"))
    )
    (net (code "149") (name "RELAY_4") (class "Default")
      (node (ref "RYS16") (pin "P$1") (pinfunction "1_P$1") (pintype "passive"))
      (node (ref "U4") (pin "55") (pinfunction "P3_13_55") (pintype "bidirectional"))
    )
    (net (code "150") (name "RELAY_5") (class "Default")
      (node (ref "RZS8") (pin "P$1") (pinfunction "1_P$1") (pintype "passive"))
      (node (ref "U4") (pin "52") (pinfunction "P2_4_52") (pintype "bidirectional"))
    )
    (net (code "151") (name "RELAY_6") (class "Default")
      (node (ref "RYS15") (pin "P$1") (pinfunction "1_P$1") (pintype "passive"))
      (node (ref "U4") (pin "51") (pinfunction "P2_5_51") (pintype "bidirectional"))
    )
    (net (code "152") (name "RELAY_7") (class "Default")
      (node (ref "RXS8") (pin "P$1") (pinfunction "1_P$1") (pintype "passive"))
      (node (ref "U4") (pin "50") (pinfunction "P2_6_50") (pintype "bidirectional"))
    )
    (net (code "153") (name "RESET") (class "Default")
      (node (ref "C57") (pin "P$1") (pinfunction "1_P$1") (pintype "passive"))
      (node (ref "J11") (pin "9") (pinfunction "9_9") (pintype "passive"))
      (node (ref "R18") (pin "P$1") (pinfunction "1_P$1") (pintype "passive"))
      (node (ref "U4") (pin "67") (pinfunction "RES#_67") (pintype "bidirectional"))
    )
    (net (code "154") (name "REXT") (class "Default")
      (node (ref "C47") (pin "P$1") (pinfunction "1_P$1") (pintype "passive"))
      (node (ref "R25") (pin "P$2") (pinfunction "2_P$2") (pintype "passive"))
      (node (ref "U3") (pin "9") (pinfunction "REXT_9") (pintype "input"))
    )
    (net (code "155") (name "RXD0") (class "Default")
      (node (ref "R31") (pin "P$2") (pinfunction "2_P$2") (pintype "passive"))
      (node (ref "U3") (pin "13") (pinfunction "RXD0_13") (pintype "bidirectional"))
    )
    (net (code "156") (name "RXD1") (class "Default")
      (node (ref "R30") (pin "P$2") (pinfunction "2_P$2") (pintype "passive"))
      (node (ref "U3") (pin "12") (pinfunction "RXD1_12") (pintype "bidirectional"))
    )
    (net (code "157") (name "RXER") (class "Default")
      (node (ref "R32") (pin "P$2") (pinfunction "2_P$2") (pintype "passive"))
      (node (ref "U3") (pin "17") (pinfunction "RXER_17") (pintype "bidirectional"))
    )
    (net (code "158") (name "RXM") (class "Default")
      (node (ref "J4") (pin "6") (pinfunction "RD-_6") (pintype "bidirectional"))
      (node (ref "U3") (pin "3") (pinfunction "RXM_3") (pintype "bidirectional"))
    )
    (net (code "159") (name "RXP") (class "Default")
      (node (ref "J4") (pin "3") (pinfunction "RD+_3") (pintype "bidirectional"))
      (node (ref "U3") (pin "4") (pinfunction "RXP_4") (pintype "bidirectional"))
    )
    (net (code "160") (name "SD1_CD") (class "Default")
      (node (ref "J9") (pin "10") (pinfunction "CD_SWITCH2_10") (pintype "bidirectional"))
      (node (ref "U4") (pin "146") (pinfunction "P5_6/AN019_146") (pintype "bidirectional"))
    )
    (net (code "161") (name "SD1_CLK") (class "Default")
      (node (ref "J9") (pin "5") (pinfunction "CLOCK_5") (pintype "bidirectional"))
      (node (ref "U4") (pin "140") (pinfunction "P5_0/AN016_140") (pintype "bidirectional"))
    )
    (net (code "162") (name "SD1_CMD") (class "Default")
      (node (ref "J9") (pin "3") (pinfunction "COMMAND/RESPONSE_3") (pintype "bidirectional"))
      (node (ref "U4") (pin "141") (pinfunction "P5_1/AN116_141") (pintype "bidirectional"))
    )
    (net (code "163") (name "SD1_DAT0") (class "Default")
      (node (ref "J9") (pin "7") (pinfunction "DATA_LINE[BIT_0]_7") (pintype "bidirectional"))
      (node (ref "U4") (pin "142") (pinfunction "P5_2/AN017_142") (pintype "bidirectional"))
    )
    (net (code "164") (name "SD1_DAT1") (class "Default")
      (node (ref "J9") (pin "8") (pinfunction "DATA_LINE[BIT_1]_8") (pintype "bidirectional"))
      (node (ref "U4") (pin "143") (pinfunction "P5_3/AN117_143") (pintype "bidirectional"))
    )
    (net (code "165") (name "SD1_DAT2") (class "Default")
      (node (ref "J9") (pin "1") (pinfunction "DATA_LINE[BIT_2]_1") (pintype "bidirectional"))
      (node (ref "U4") (pin "144") (pinfunction "P5_4/AN018_144") (pintype "bidirectional"))
    )
    (net (code "166") (name "SD1_DAT3") (class "Default")
      (node (ref "J9") (pin "2") (pinfunction "CARD_DETECT/DATA_LINE[BIT_3]_2") (pintype "bidirectional"))
      (node (ref "U4") (pin "145") (pinfunction "P5_5/AN118_145") (pintype "bidirectional"))
    )
    (net (code "167") (name "SD1_WP") (class "Default")
      (node (ref "J9") (pin "9") (pinfunction "CD_SWITCH1_9") (pintype "bidirectional"))
      (node (ref "U4") (pin "147") (pinfunction "P5_7/AN119_147") (pintype "bidirectional"))
    )
    (net (code "168") (name "TCK") (class "Default")
      (node (ref "J11") (pin "7") (pinfunction "7_7") (pintype "passive"))
      (node (ref "U4") (pin "88") (pinfunction "P3_0_88") (pintype "bidirectional"))
    )
    (net (code "169") (name "TDI") (class "Default")
      (node (ref "J11") (pin "1") (pinfunction "1_1") (pintype "passive"))
      (node (ref "U4") (pin "91") (pinfunction "P1_10_91") (pintype "bidirectional"))
    )
    (net (code "170") (name "TDO") (class "Default")
      (node (ref "J11") (pin "3") (pinfunction "3_3") (pintype "passive"))
      (node (ref "U4") (pin "90") (pinfunction "P1_9_90") (pintype "bidirectional"))
    )
    (net (code "171") (name "TMS") (class "Default")
      (node (ref "J11") (pin "5") (pinfunction "5_5") (pintype "passive"))
      (node (ref "U4") (pin "89") (pinfunction "P1_8_89") (pintype "bidirectional"))
    )
    (net (code "172") (name "TXM") (class "Default")
      (node (ref "J4") (pin "2") (pinfunction "TD-_2") (pintype "bidirectional"))
      (node (ref "U3") (pin "5") (pinfunction "TXM_5") (pintype "bidirectional"))
    )
    (net (code "173") (name "TXP") (class "Default")
      (node (ref "J4") (pin "1") (pinfunction "TD+_1") (pintype "bidirectional"))
      (node (ref "U3") (pin "6") (pinfunction "TXP_6") (pintype "bidirectional"))
    )
    (net (code "174") (name "USBHS_FAULT") (class "Default")
      (node (ref "R12") (pin "P$1") (pinfunction "1_P$1") (pintype "passive"))
      (node (ref "U2") (pin "3") (pinfunction "FLG_3") (pintype "input"))
      (node (ref "U4") (pin "78") (pinfunction "P3_8_78") (pintype "bidirectional"))
    )
    (net (code "175") (name "USBHS_N") (class "Default")
      (node (ref "J3") (pin "D-") (pinfunction "D-_D-") (pintype "bidirectional"))
      (node (ref "U4") (pin "31") (pinfunction "USBHS_DM_31") (pintype "bidirectional"))
    )
    (net (code "176") (name "USBHS_P") (class "Default")
      (node (ref "J3") (pin "D+") (pinfunction "D+_D+") (pintype "bidirectional"))
      (node (ref "U4") (pin "32") (pinfunction "USBHS_DP_32") (pintype "bidirectional"))
    )
    (net (code "177") (name "USBHS_VBUS") (class "Default")
      (node (ref "C11") (pin "P$1") (pinfunction "1_P$1") (pintype "passive"))
      (node (ref "C15") (pin "1") (pinfunction "1_1") (pintype "passive"))
      (node (ref "J3") (pin "VBUS") (pinfunction "VBUS_VBUS") (pintype "power_in"))
      (node (ref "U2") (pin "5") (pinfunction "OUT_5") (pintype "input"))
      (node (ref "U4") (pin "17") (pinfunction "PB_1_17") (pintype "bidirectional"))
    )
    (net (code "178") (name "USBHS_VBUSEN") (class "Default")
      (node (ref "R1") (pin "P$1") (pinfunction "1_P$1") (pintype "passive"))
      (node (ref "U2") (pin "1") (pinfunction "EN_1") (pintype "input"))
    )
    (net (code "179") (name "USB_N") (class "Default")
      (node (ref "R5") (pin "P$1") (pinfunction "1_P$1") (pintype "passive"))
      (node (ref "U4") (pin "46") (pinfunction "USB_DM_46") (pintype "bidirectional"))
    )
    (net (code "180") (name "USB_P") (class "Default")
      (node (ref "R6") (pin "P$1") (pinfunction "1_P$1") (pintype "passive"))
      (node (ref "U4") (pin "47") (pinfunction "USB_DP_47") (pintype "bidirectional"))
    )
    (net (code "181") (name "USB_VBUS_B") (class "Default")
      (node (ref "R4") (pin "P$1") (pinfunction "1_P$1") (pintype "passive"))
      (node (ref "U4") (pin "44") (pinfunction "P4_7_44") (pintype "bidirectional"))
    )
    (net (code "182") (name "VCL_F(FLASH)") (class "Default")
      (node (ref "C36") (pin "P$2") (pinfunction "2_P$2") (pintype "passive"))
      (node (ref "U4") (pin "112") (pinfunction "VCL_F(FLASH)_112") (pintype "bidirectional"))
    )
    (net (code "183") (name "VDD") (class "Default")
      (node (ref "C10") (pin "P$2") (pinfunction "2_P$2") (pintype "passive"))
      (node (ref "C13") (pin "P$2") (pinfunction "2_P$2") (pintype "passive"))
      (node (ref "C14") (pin "P$2") (pinfunction "2_P$2") (pintype "passive"))
      (node (ref "C30") (pin "P$2") (pinfunction "2_P$2") (pintype "passive"))
      (node (ref "C32") (pin "P$1") (pinfunction "1_P$1") (pintype "passive"))
      (node (ref "C33") (pin "P$1") (pinfunction "1_P$1") (pintype "passive"))
      (node (ref "C34") (pin "P$1") (pinfunction "1_P$1") (pintype "passive"))
      (node (ref "C35") (pin "P$1") (pinfunction "1_P$1") (pintype "passive"))
      (node (ref "C48") (pin "1") (pinfunction "1_1") (pintype "passive"))
      (node (ref "C49") (pin "P$1") (pinfunction "1_P$1") (pintype "passive"))
      (node (ref "C54") (pin "P$2") (pinfunction "2_P$2") (pintype "passive"))
      (node (ref "C55") (pin "P$2") (pinfunction "2_P$2") (pintype "passive"))
      (node (ref "C56") (pin "P$2") (pinfunction "2_P$2") (pintype "passive"))
      (node (ref "C58") (pin "P$1") (pinfunction "1_P$1") (pintype "passive"))
      (node (ref "C59") (pin "P$1") (pinfunction "1_P$1") (pintype "passive"))
      (node (ref "C60") (pin "P$1") (pinfunction "1_P$1") (pintype "passive"))
      (node (ref "C61") (pin "P$2") (pinfunction "2_P$2") (pintype "passive"))
      (node (ref "FB2/2") (pin "1") (pinfunction "P$1_1") (pintype "bidirectional"))
      (node (ref "J11") (pin "2") (pinfunction "2_2") (pintype "passive"))
      (node (ref "J11") (pin "4") (pinfunction "4_4") (pintype "passive"))
      (node (ref "J9") (pin "4") (pinfunction "SUPPLY_VOLTAGE_4") (pintype "power_in"))
      (node (ref "L3") (pin "2") (pinfunction "P$2_2") (pintype "bidirectional"))
      (node (ref "R10") (pin "P$1") (pinfunction "1_P$1") (pintype "passive"))
      (node (ref "R11") (pin "P$1") (pinfunction "1_P$1") (pintype "passive"))
      (node (ref "R13") (pin "P$2") (pinfunction "2_P$2") (pintype "passive"))
      (node (ref "R14") (pin "P$1") (pinfunction "1_P$1") (pintype "passive"))
      (node (ref "R18") (pin "P$2") (pinfunction "2_P$2") (pintype "passive"))
      (node (ref "R2") (pin "P$1") (pinfunction "1_P$1") (pintype "passive"))
      (node (ref "R20") (pin "P$1") (pinfunction "1_P$1") (pintype "passive"))
      (node (ref "R21") (pin "P$1") (pinfunction "1_P$1") (pintype "passive"))
      (node (ref "R23") (pin "P$2") (pinfunction "2_P$2") (pintype "passive"))
      (node (ref "R24") (pin "P$2") (pinfunction "2_P$2") (pintype "passive"))
      (node (ref "R26") (pin "P$2") (pinfunction "2_P$2") (pintype "passive"))
      (node (ref "R27") (pin "P$2") (pinfunction "2_P$2") (pintype "passive"))
      (node (ref "R28") (pin "P$2") (pinfunction "2_P$2") (pintype "passive"))
      (node (ref "R29") (pin "P$2") (pinfunction "2_P$2") (pintype "passive"))
      (node (ref "R3") (pin "P$1") (pinfunction "1_P$1") (pintype "passive"))
      (node (ref "R8") (pin "P$1") (pinfunction "1_P$1") (pintype "passive"))
      (node (ref "R9") (pin "P$1") (pinfunction "1_P$1") (pintype "passive"))
      (node (ref "U3") (pin "14") (pinfunction "VDDIO_14") (pintype "power_in"))
      (node (ref "U4") (pin "110") (pinfunction "VCC(IO)5_110") (pintype "bidirectional"))
      (node (ref "U4") (pin "123") (pinfunction "VCC(IO)6_123") (pintype "bidirectional"))
      (node (ref "U4") (pin "138") (pinfunction "VCC(IO)7_138") (pintype "bidirectional"))
      (node (ref "U4") (pin "149") (pinfunction "VCC(IO)8_149") (pintype "bidirectional"))
      (node (ref "U4") (pin "155") (pinfunction "AVCC0_155") (pintype "bidirectional"))
      (node (ref "U4") (pin "171") (pinfunction "VCC(IO)9_171") (pintype "bidirectional"))
      (node (ref "U4") (pin "25") (pinfunction "VCC1_25") (pintype "bidirectional"))
      (node (ref "U4") (pin "26") (pinfunction "AVCC_SUBHS_26") (pintype "bidirectional"))
      (node (ref "U4") (pin "34") (pinfunction "VCC_USBHS_34") (pintype "bidirectional"))
      (node (ref "U4") (pin "48") (pinfunction "VCC_USB_48") (pintype "bidirectional"))
      (node (ref "U4") (pin "61") (pinfunction "VCC(IO)2_61") (pintype "bidirectional"))
      (node (ref "U4") (pin "84") (pinfunction "VCC(IO)3_84") (pintype "bidirectional"))
      (node (ref "U4") (pin "97") (pinfunction "VCC(IO)4_97") (pintype "bidirectional"))
    )
    (net (code "184") (name "VDD5") (class "Default")
      (node (ref "C5") (pin "P$1") (pinfunction "1_P$1") (pintype "passive"))
      (node (ref "C8") (pin "P$1") (pinfunction "1_P$1") (pintype "passive"))
      (node (ref "J1") (pin "5") (pinfunction "5_5") (pintype "passive"))
      (node (ref "J1") (pin "6") (pinfunction "6_6") (pintype "passive"))
      (node (ref "R1") (pin "P$2") (pinfunction "2_P$2") (pintype "passive"))
      (node (ref "R12") (pin "P$2") (pinfunction "2_P$2") (pintype "passive"))
      (node (ref "U2") (pin "4") (pinfunction "VIN_4") (pintype "input"))
    )
    (net (code "185") (name "VDD12") (class "Default")
      (node (ref "J1") (pin "7") (pinfunction "7_7") (pintype "passive"))
      (node (ref "J1") (pin "8") (pinfunction "8_8") (pintype "passive"))
    )
    (net (code "186") (name "VDDIN") (class "Default")
      (node (ref "J1") (pin "3") (pinfunction "3_3") (pintype "passive"))
      (node (ref "J1") (pin "4") (pinfunction "4_4") (pintype "passive"))
      (node (ref "L3") (pin "1") (pinfunction "P$1_1") (pintype "bidirectional"))
    )
    (net (code "187") (name "VDD_1.2") (class "Default")
      (node (ref "C45") (pin "P$1") (pinfunction "1_P$1") (pintype "passive"))
      (node (ref "C46") (pin "P$1") (pinfunction "1_P$1") (pintype "passive"))
      (node (ref "U3") (pin "1") (pinfunction "VDD_1.2_1") (pintype "power_in"))
    )
    (net (code "188") (name "XCIN") (class "Default")
      (node (ref "C50") (pin "P$1") (pinfunction "1_P$1") (pintype "passive"))
      (node (ref "U4") (pin "20") (pinfunction "XCIN_20") (pintype "bidirectional"))
      (node (ref "X3") (pin "P$1") (pinfunction "P$1_P$1") (pintype "bidirectional"))
    )
    (net (code "189") (name "XCOUT") (class "Default")
      (node (ref "C51") (pin "P$1") (pinfunction "1_P$1") (pintype "passive"))
      (node (ref "U4") (pin "21") (pinfunction "XCOUT_21") (pintype "bidirectional"))
      (node (ref "X3") (pin "P$2") (pinfunction "P$2_P$2") (pintype "bidirectional"))
    )
    (net (code "190") (name "XII") (class "Default")
      (node (ref "C42") (pin "P$1") (pinfunction "1_P$1") (pintype "passive"))
      (node (ref "U$3") (pin "1") (pinfunction "1_1") (pintype "bidirectional"))
      (node (ref "U3") (pin "8") (pinfunction "XI_8") (pintype "input"))
    )
    (net (code "191") (name "XOO") (class "Default")
      (node (ref "C41") (pin "P$1") (pinfunction "1_P$1") (pintype "passive"))
      (node (ref "U$3") (pin "3") (pinfunction "3_3") (pintype "bidirectional"))
      (node (ref "U3") (pin "7") (pinfunction "XO_7") (pintype "output"))
    )
    (net (code "192") (name "XTAL1") (class "Default")
      (node (ref "C52") (pin "P$1") (pinfunction "1_P$1") (pintype "passive"))
      (node (ref "U4") (pin "23") (pinfunction "P2_13/XTAL_23") (pintype "bidirectional"))
      (node (ref "X4") (pin "1") (pinfunction "1_1") (pintype "bidirectional"))
    )
    (net (code "193") (name "XTAL2") (class "Default")
      (node (ref "C53") (pin "P$1") (pinfunction "1_P$1") (pintype "passive"))
      (node (ref "U4") (pin "24") (pinfunction "P2_12/EXTAL_24") (pintype "bidirectional"))
      (node (ref "X4") (pin "3") (pinfunction "3_3") (pintype "bidirectional"))
    )
    (net (code "194") (name "unconnected-(U4-VREFH-Pad154)") (class "Default")
      (node (ref "U4") (pin "154") (pinfunction "VREFH_154") (pintype "bidirectional"))
    )
    (net (code "195") (name "unconnected-(U4-VREFH0-Pad158)") (class "Default")
      (node (ref "U4") (pin "158") (pinfunction "VREFH0_158") (pintype "bidirectional"))
    )
    (net (code "196") (name "unconnected-(U4-VREFL-Pad153)") (class "Default")
      (node (ref "U4") (pin "153") (pinfunction "VREFL_153") (pintype "bidirectional"))
    )
    (net (code "197") (name "unconnected-(U4-VREFL0-Pad157)") (class "Default")
      (node (ref "U4") (pin "157") (pinfunction "VREFL0_157") (pintype "bidirectional"))
    )
  )
)
